# Solo_MultiCharger.net
KiCad netlist of a schematic drawn in EAGLE
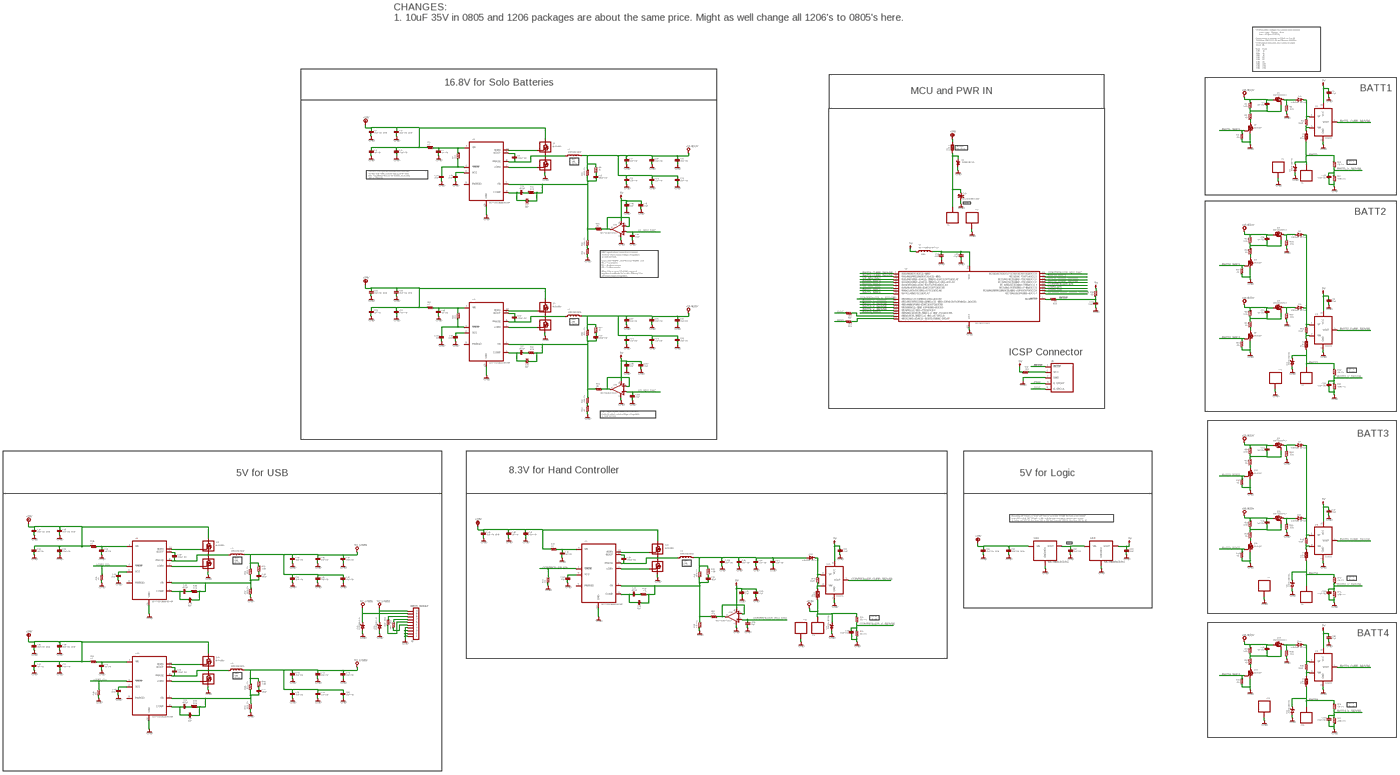
[diagram p0: schematic, sheet 1, overview]
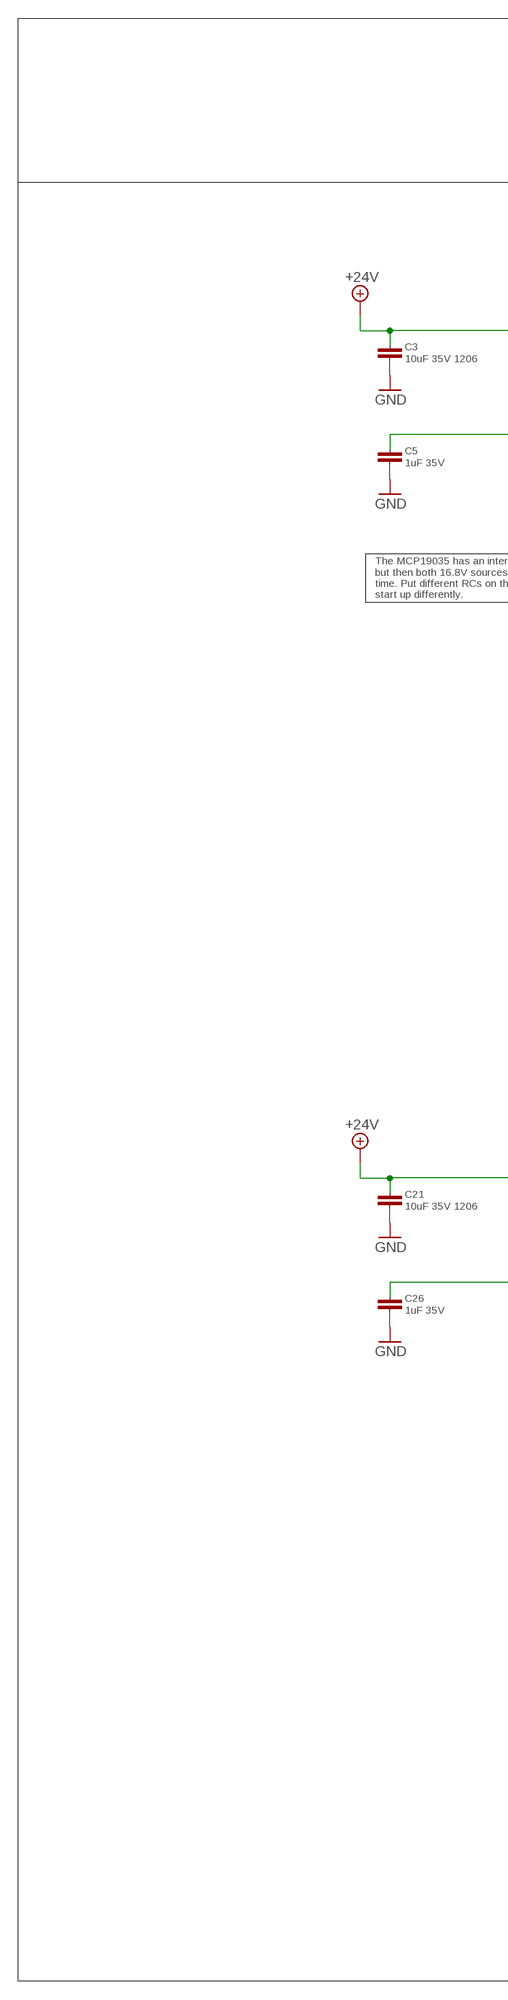
[diagram p1: schematic, sheet 1, part 1 of 8]
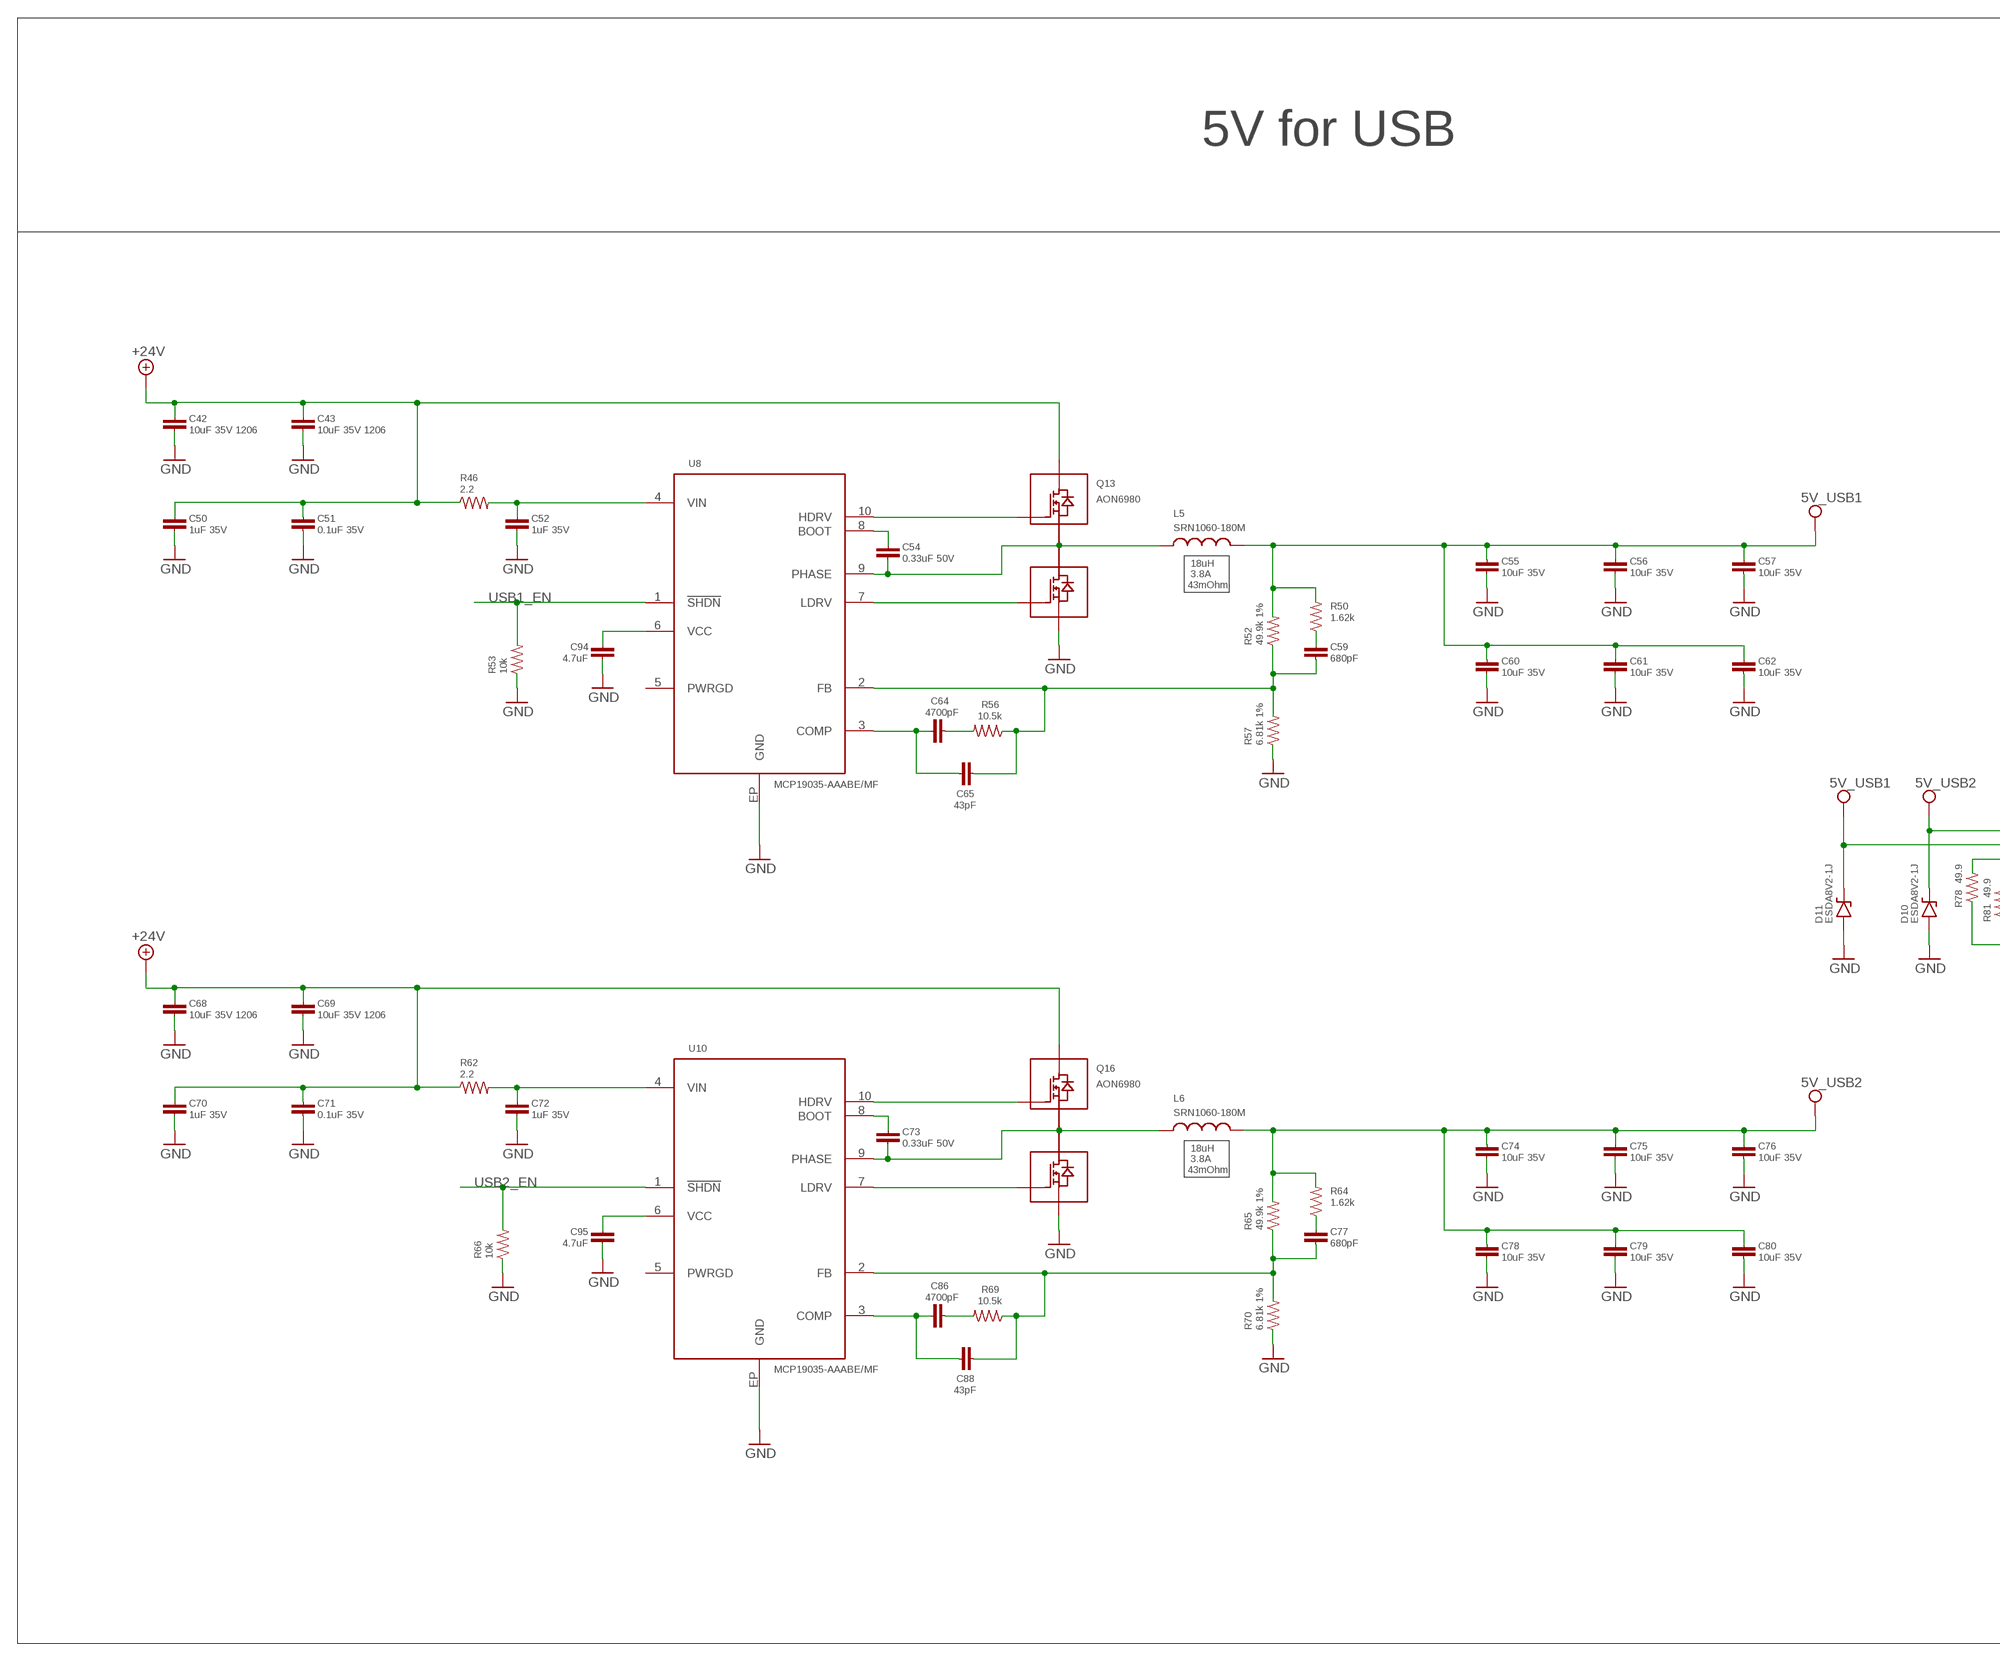
[diagram p2: schematic, sheet 1, part 2 of 8]
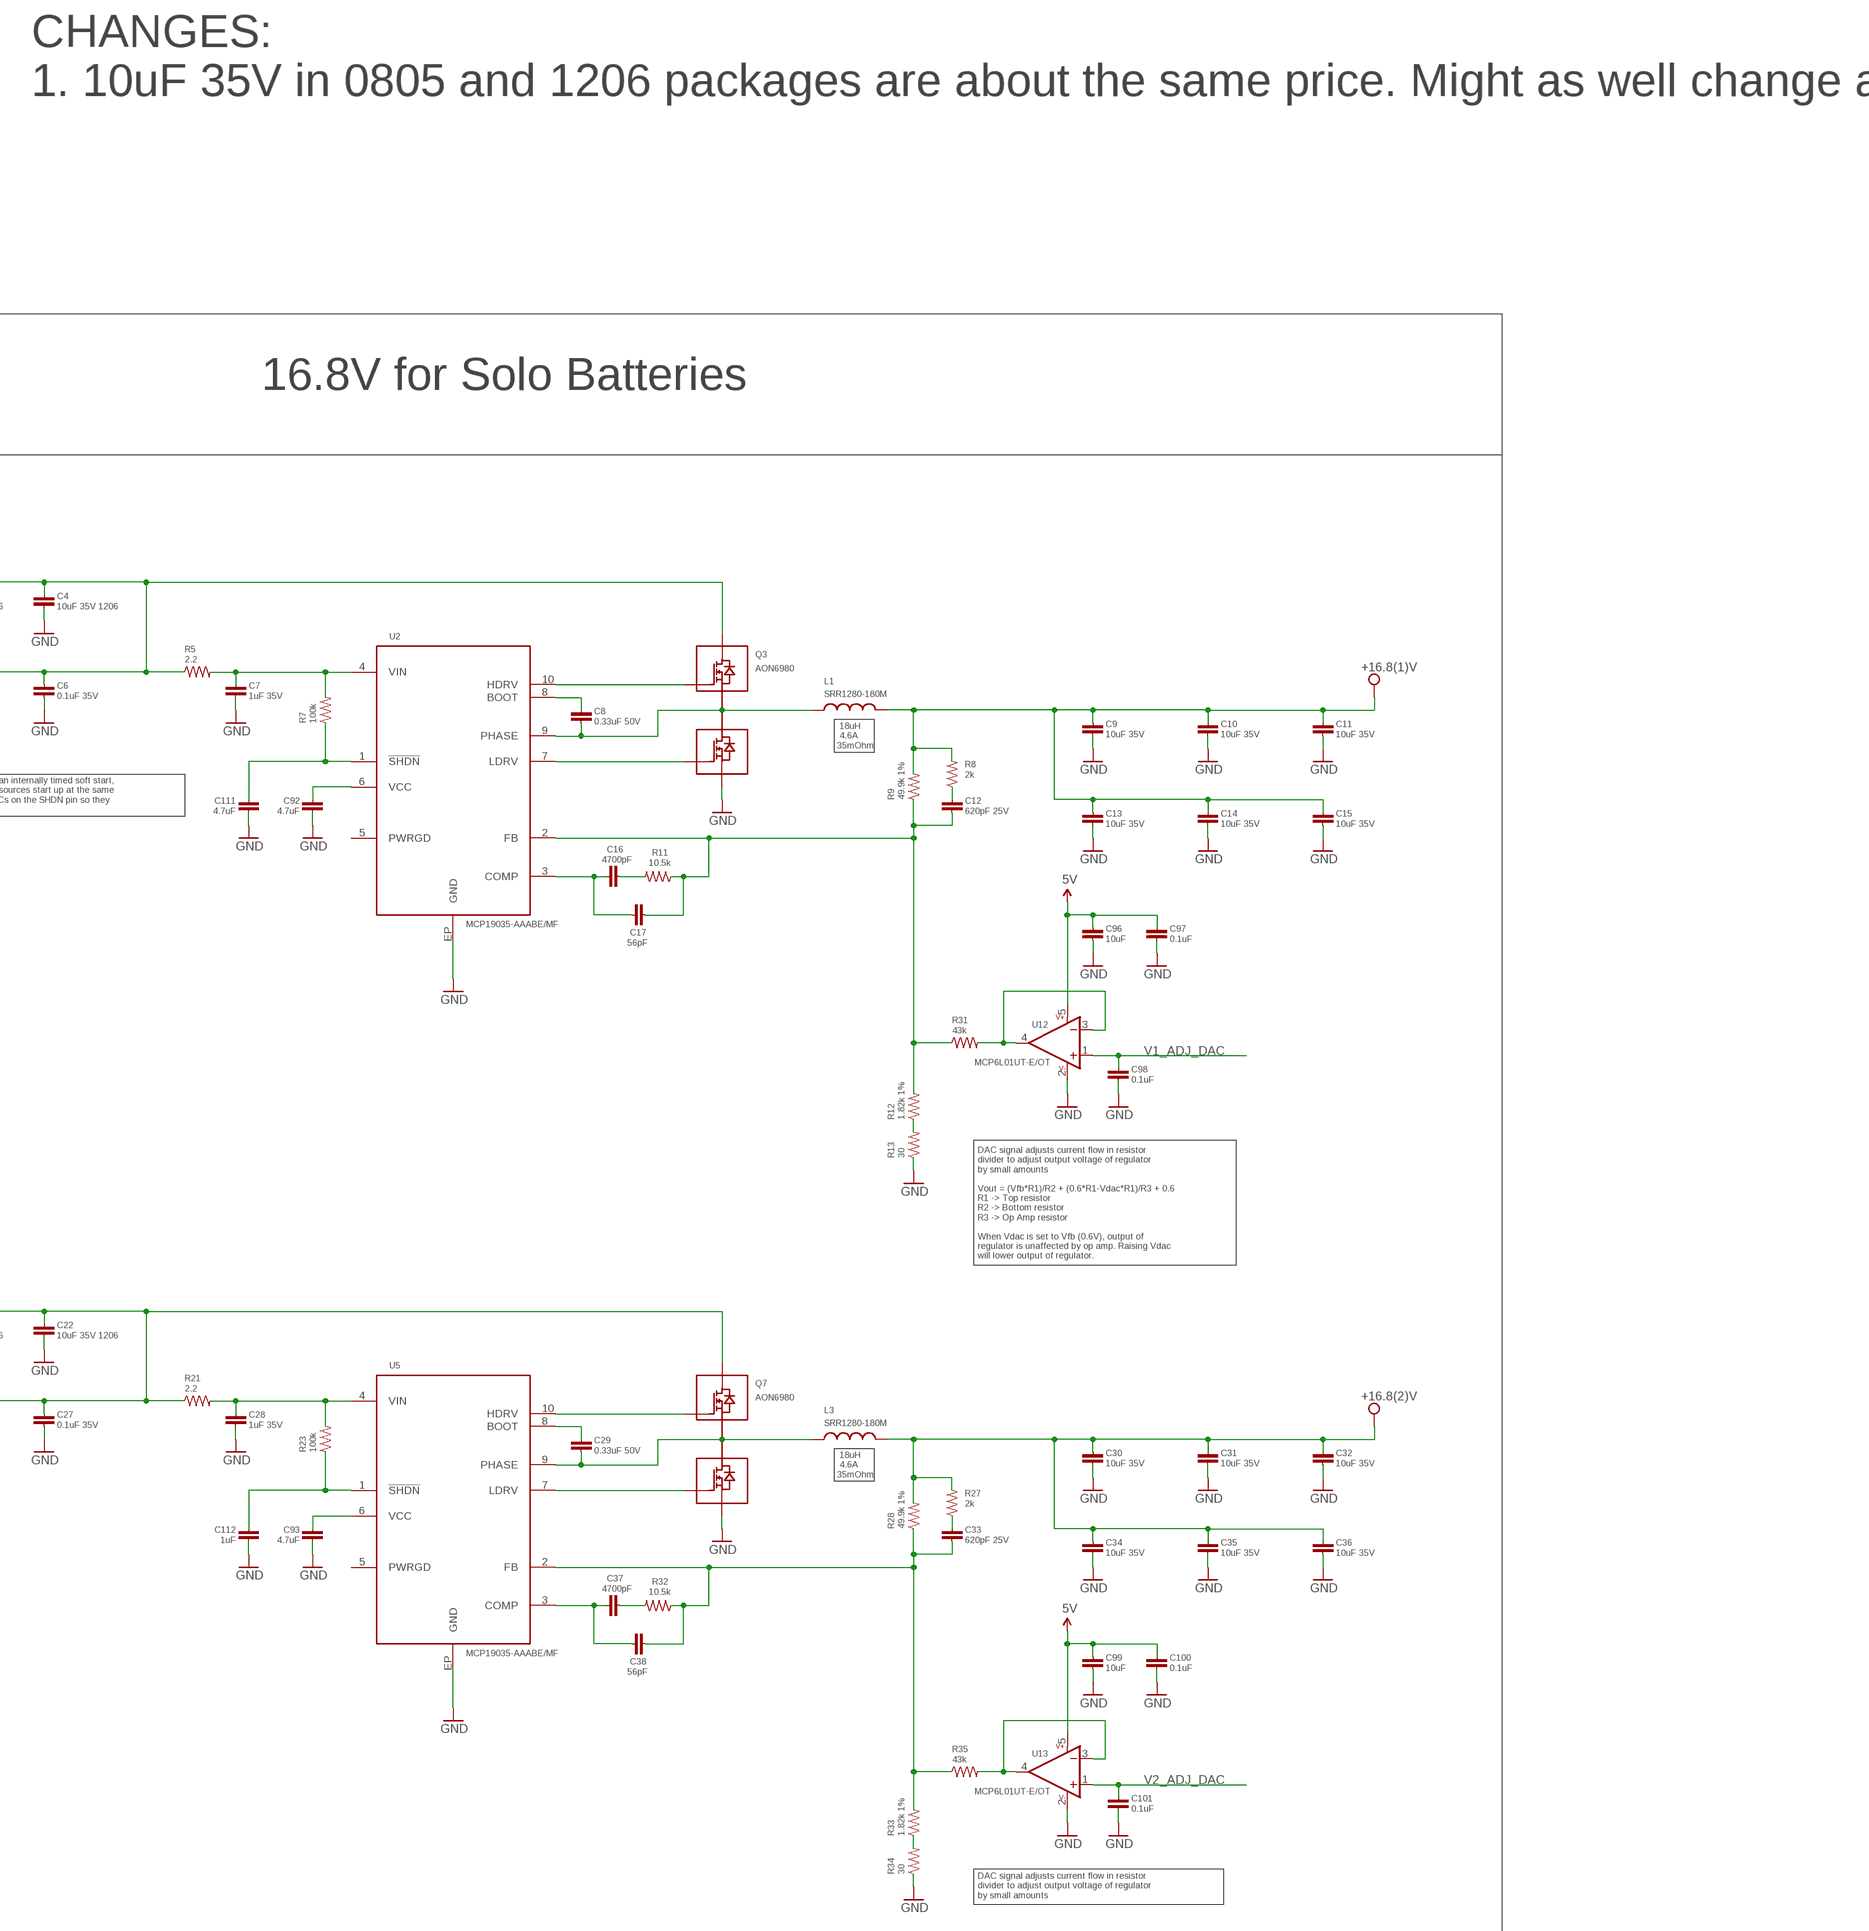
[diagram p3: schematic, sheet 1, part 3 of 8]
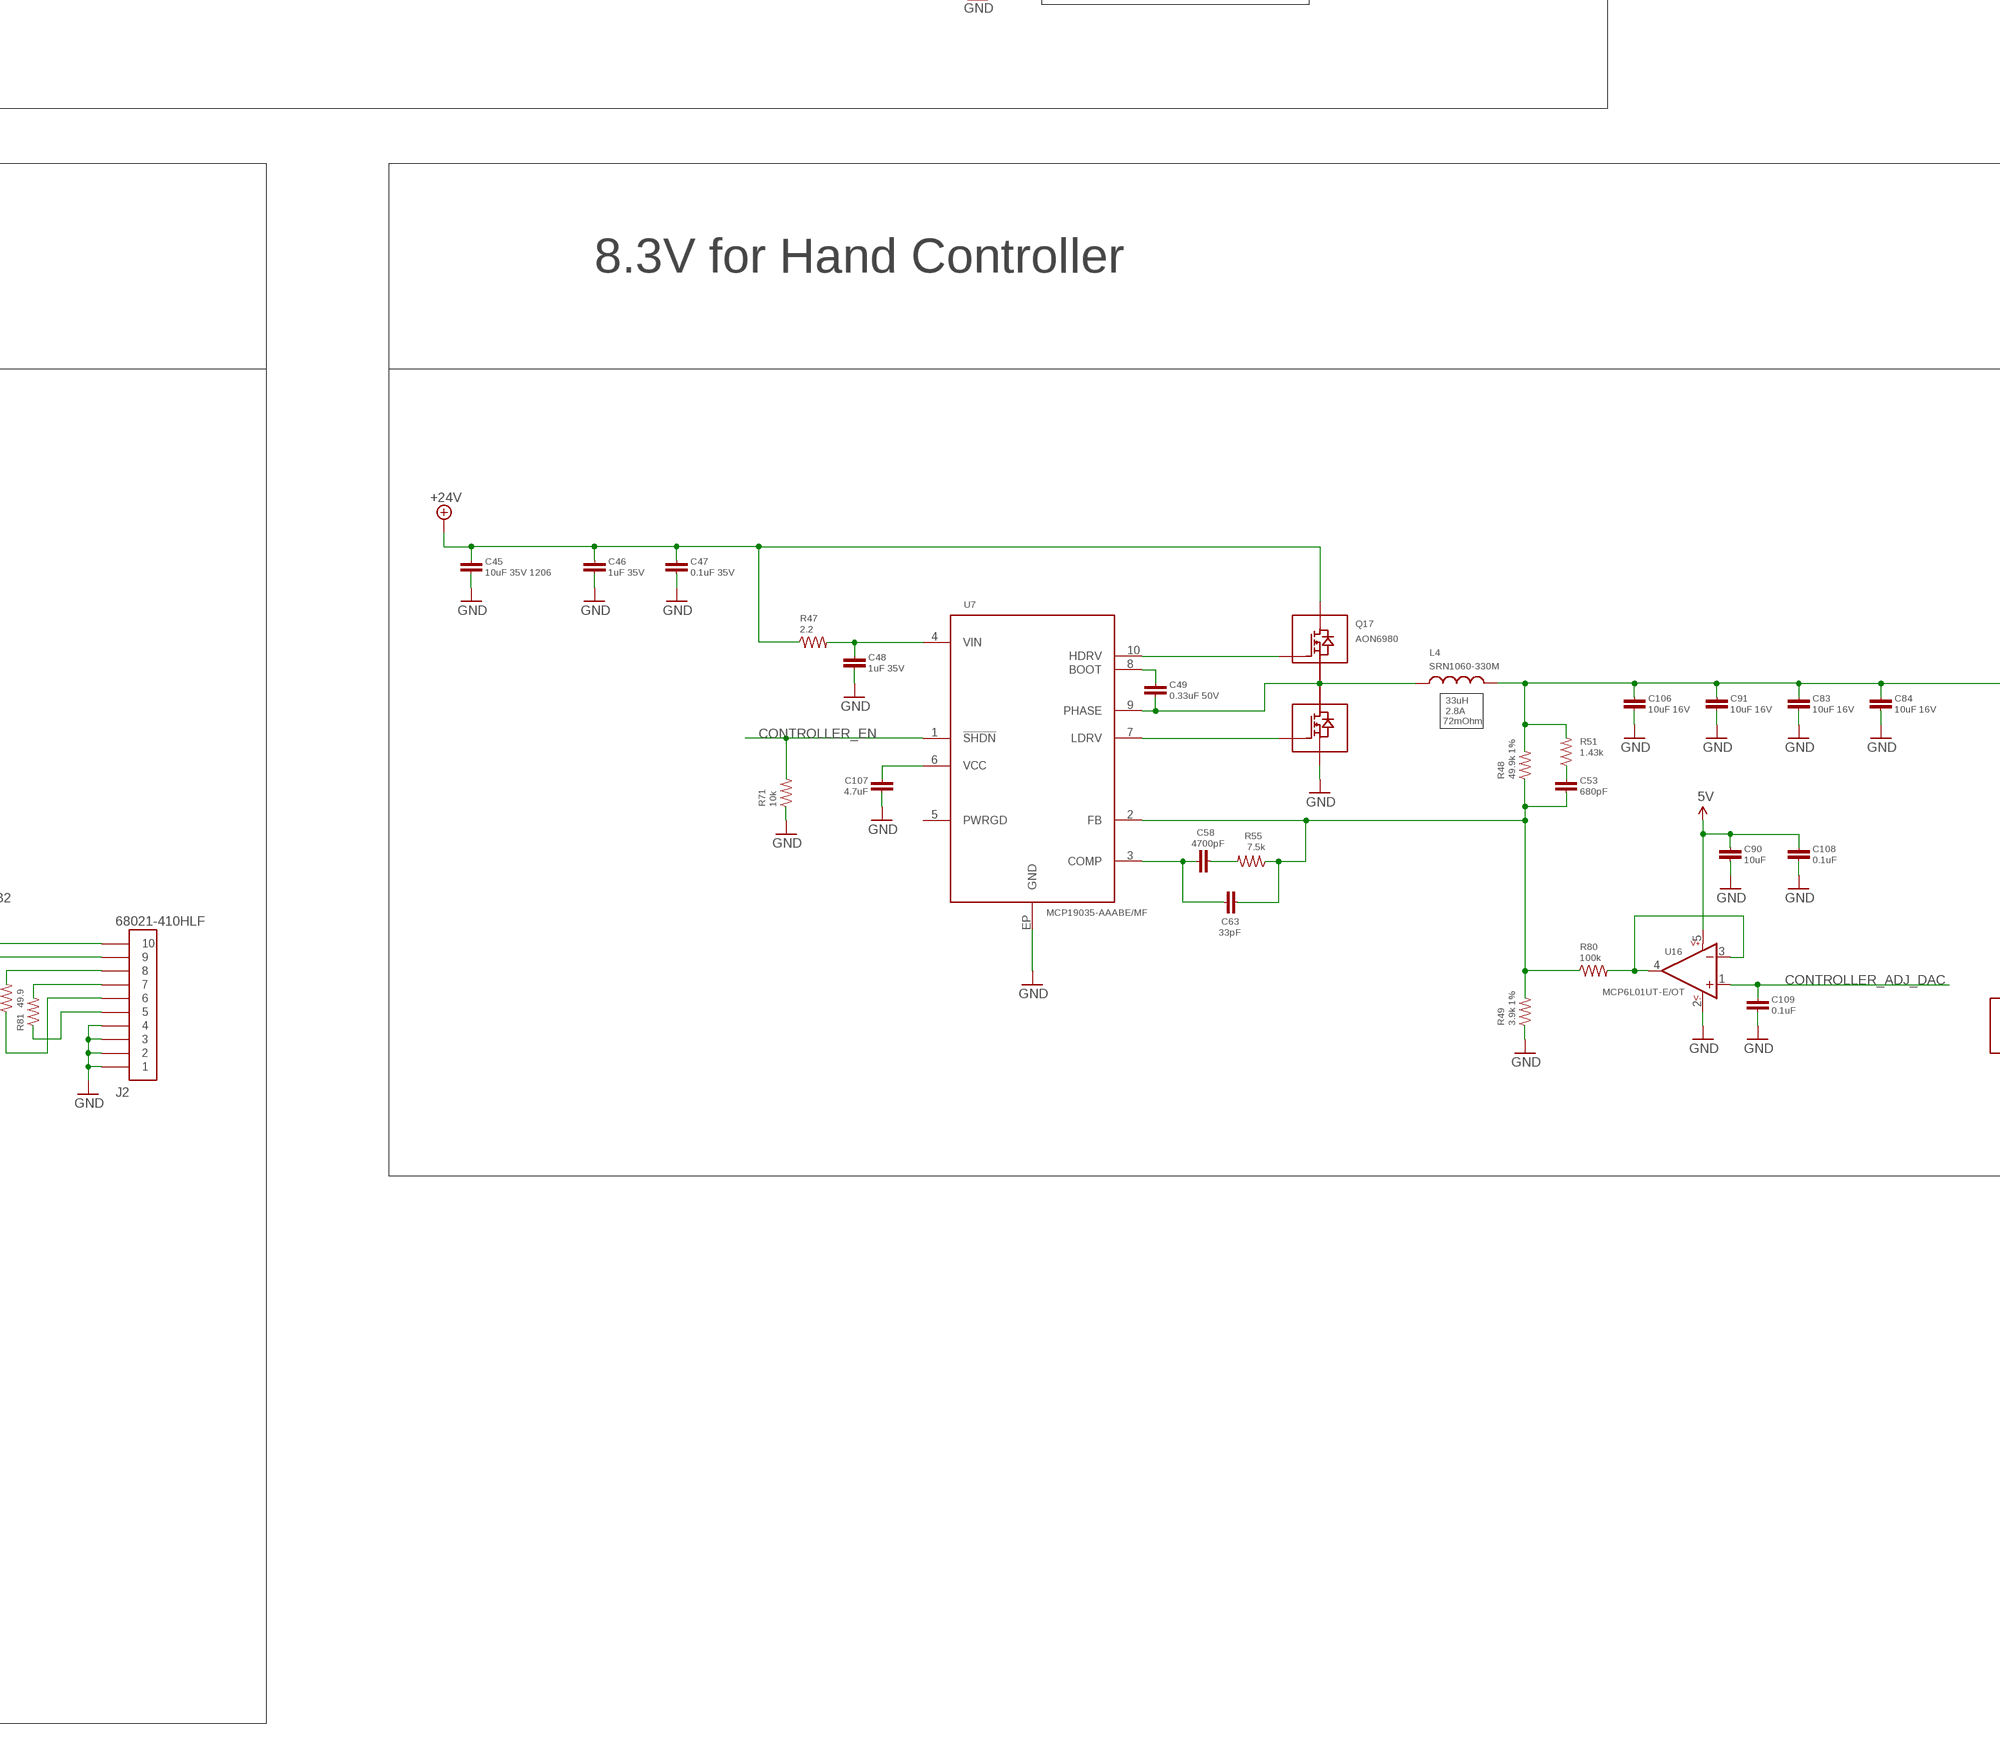
[diagram p4: schematic, sheet 1, part 4 of 8]
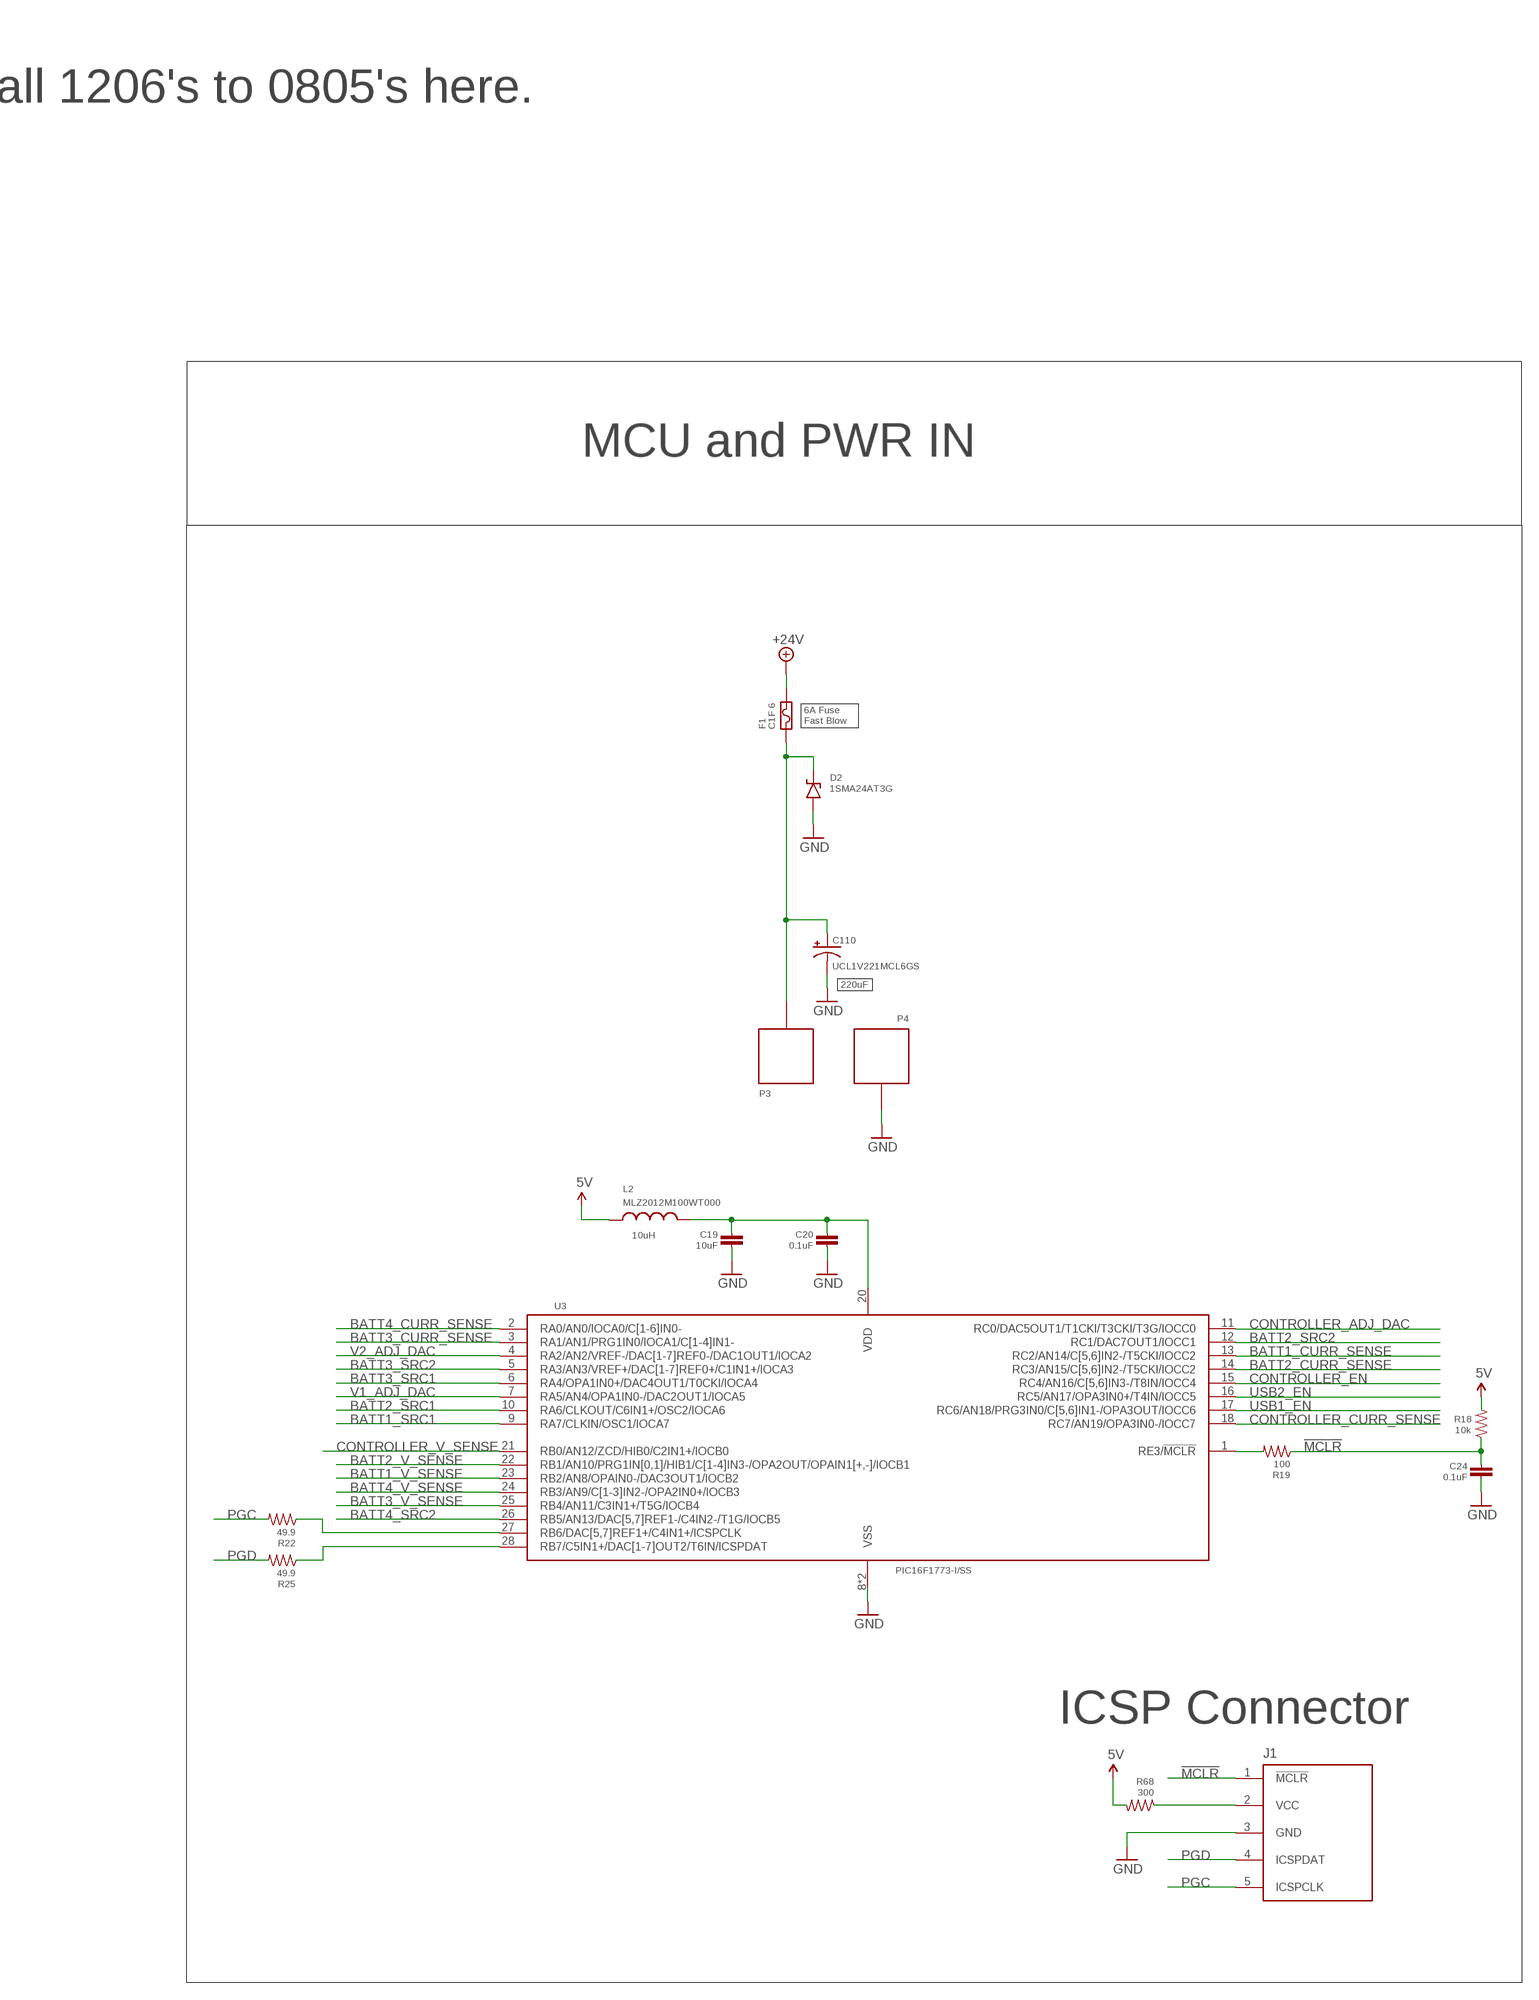
[diagram p5: schematic, sheet 1, part 5 of 8]
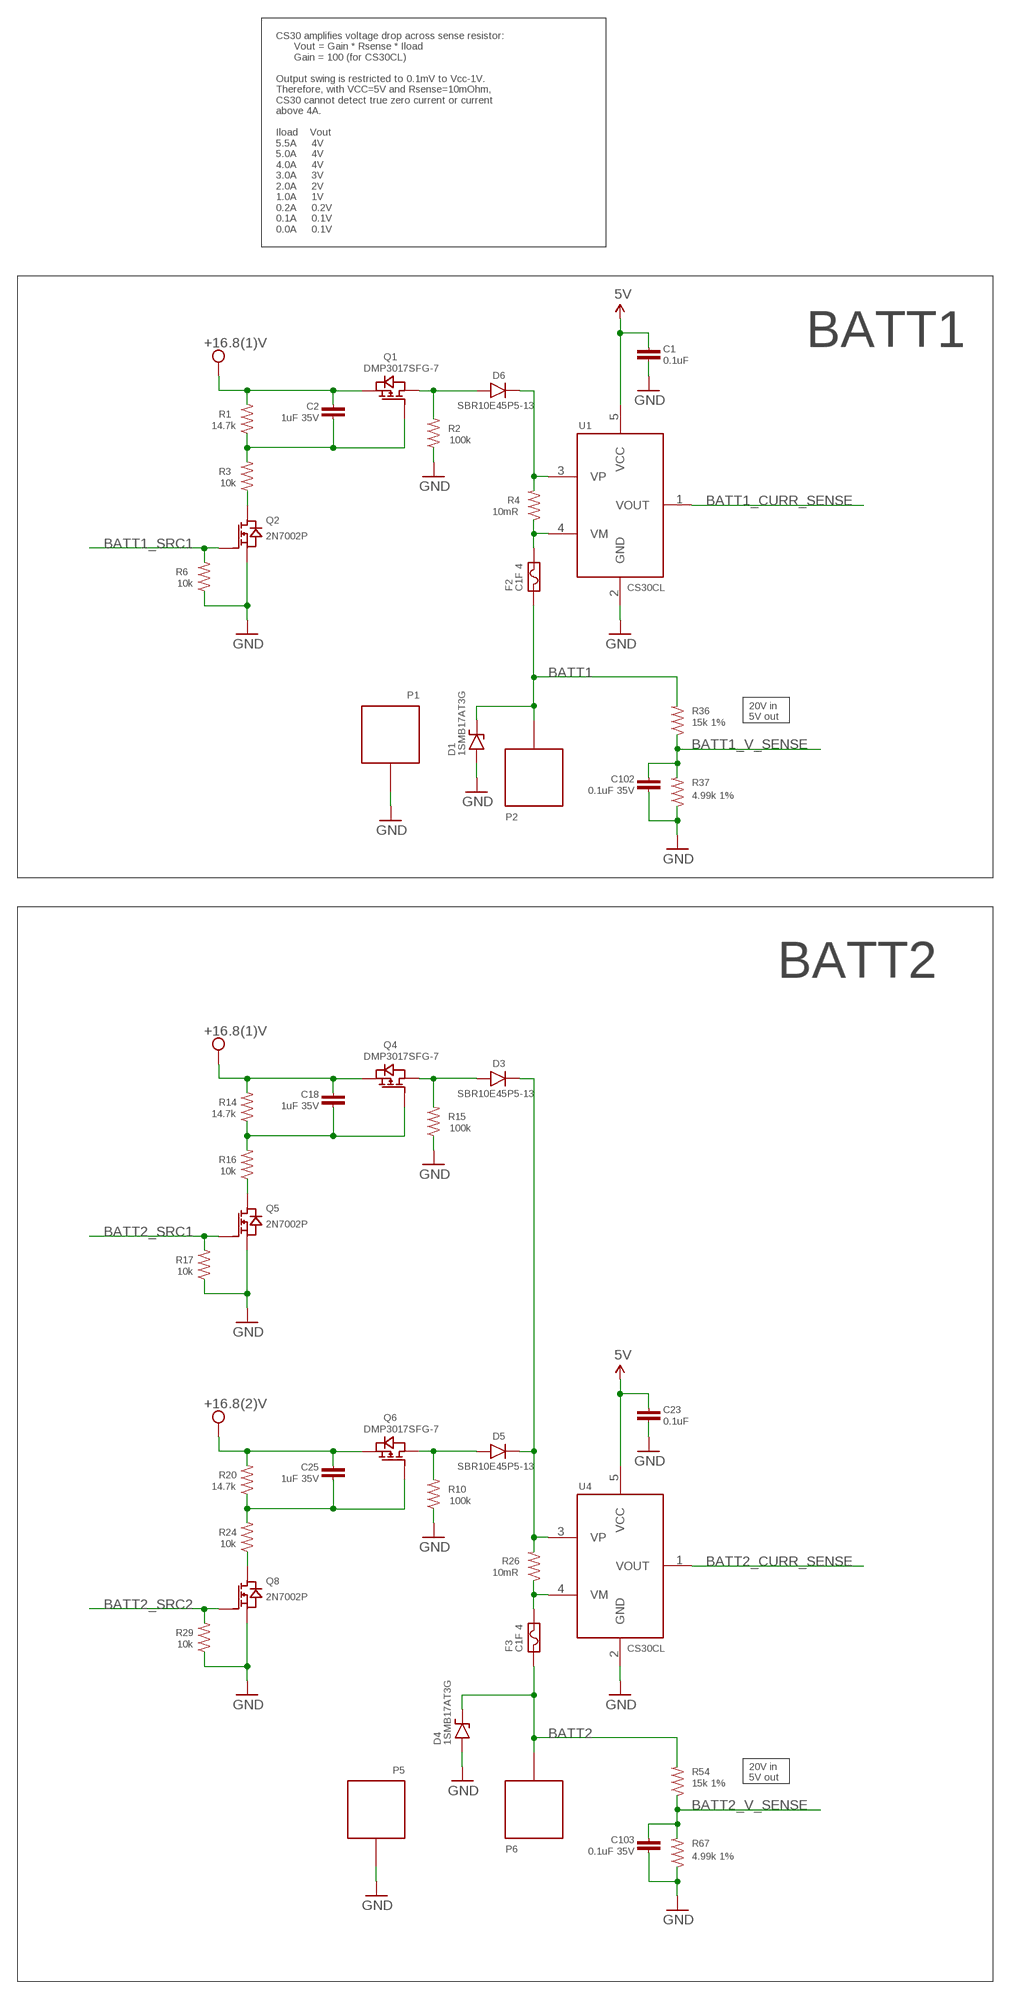
[diagram p6: schematic, sheet 1, part 6 of 8]
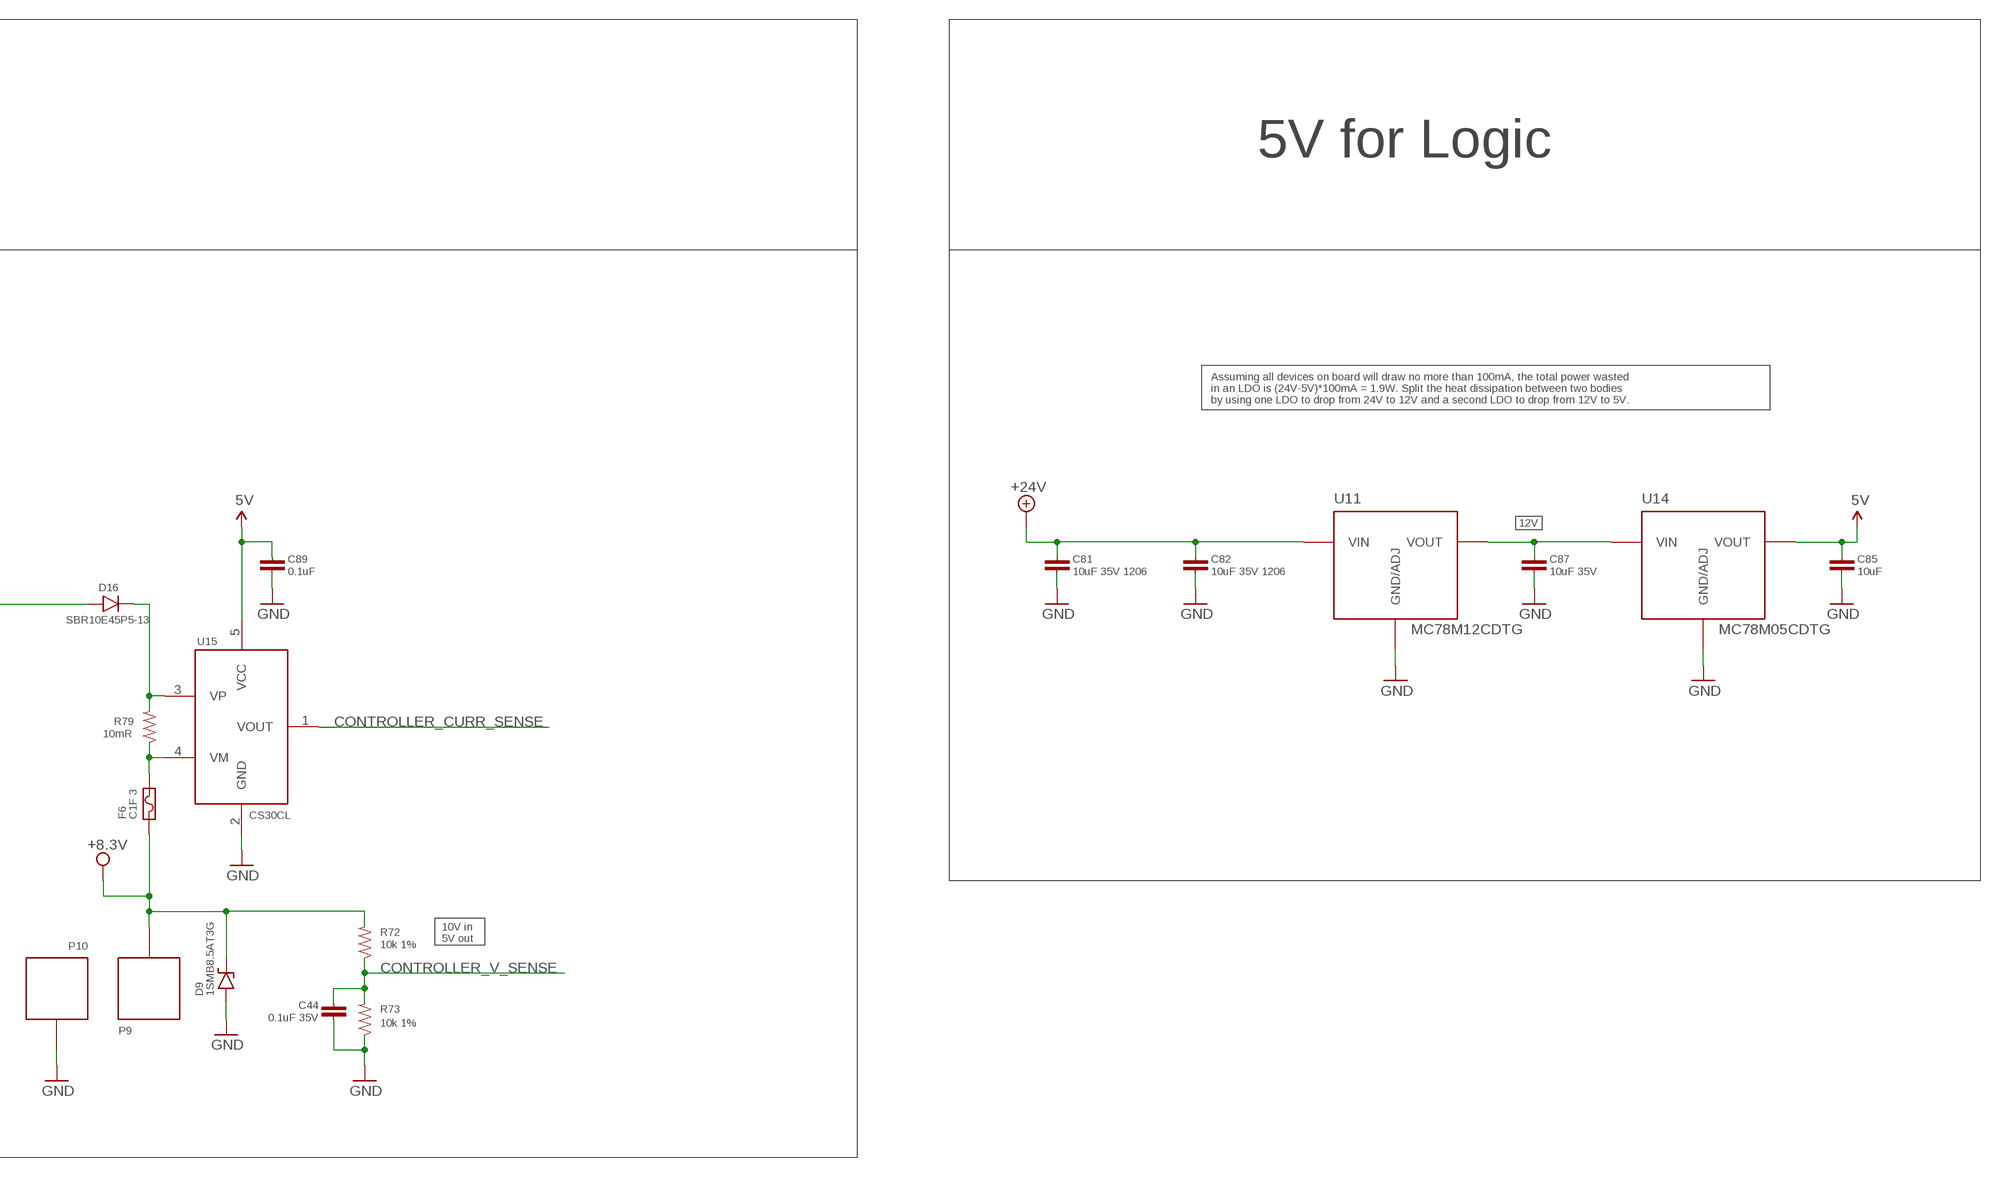
[diagram p7: schematic, sheet 1, part 7 of 8]
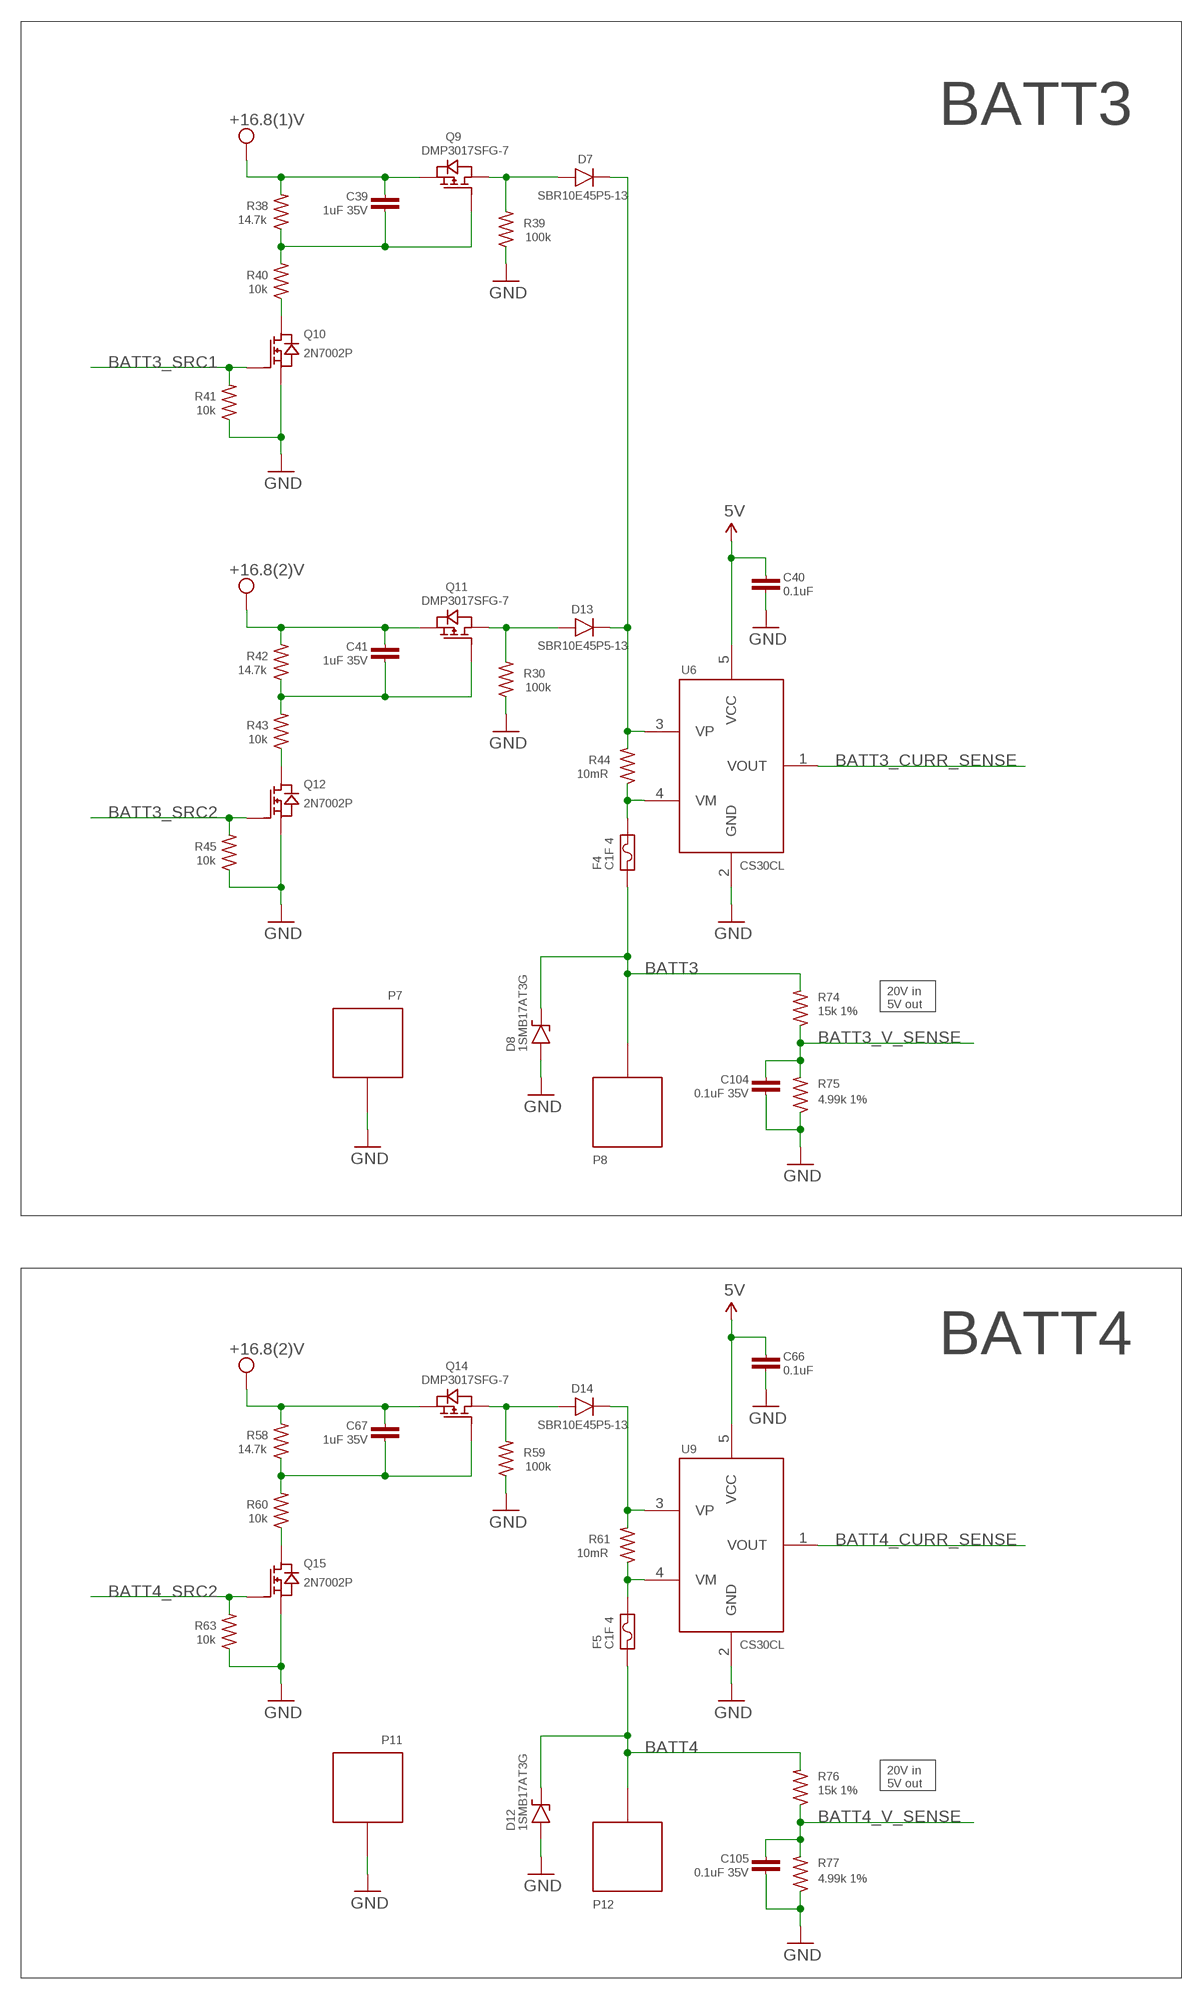
[diagram p8: schematic, sheet 1, part 8 of 8]

(export (version "E")
  (design (tool "Eeschema 10.0.6"))
  (components
    (comp (ref "C1")
      (value "0.1uF")
      (footprint "eagle-import:0805")
      (libsource (lib "eagle-import") (part "CAP_(4)"))
    )
    (comp (ref "C2")
      (value "1uF 35V")
      (footprint "eagle-import:0805")
      (libsource (lib "eagle-import") (part "CAP_(4)"))
    )
    (comp (ref "C3")
      (value "10uF 35V 1206")
      (footprint "eagle-import:1206")
      (libsource (lib "eagle-import") (part "CAP_(5)"))
    )
    (comp (ref "C4")
      (value "10uF 35V 1206")
      (footprint "eagle-import:1206")
      (libsource (lib "eagle-import") (part "CAP_(5)"))
    )
    (comp (ref "C5")
      (value "1uF 35V")
      (footprint "eagle-import:0805")
      (libsource (lib "eagle-import") (part "CAP_(4)"))
    )
    (comp (ref "C6")
      (value "0.1uF 35V")
      (footprint "eagle-import:0805")
      (libsource (lib "eagle-import") (part "CAP_(4)"))
    )
    (comp (ref "C7")
      (value "1uF 35V")
      (footprint "eagle-import:0805")
      (libsource (lib "eagle-import") (part "CAP_(4)"))
    )
    (comp (ref "C8")
      (value "0.33uF 50V")
      (footprint "eagle-import:0805")
      (libsource (lib "eagle-import") (part "CAP_(4)"))
    )
    (comp (ref "C9")
      (value "10uF 35V")
      (footprint "eagle-import:0805")
      (libsource (lib "eagle-import") (part "CAP_(4)"))
    )
    (comp (ref "C10")
      (value "10uF 35V")
      (footprint "eagle-import:0805")
      (libsource (lib "eagle-import") (part "CAP_(4)"))
    )
    (comp (ref "C11")
      (value "10uF 35V")
      (footprint "eagle-import:0805")
      (libsource (lib "eagle-import") (part "CAP_(4)"))
    )
    (comp (ref "C12")
      (value "620pF 25V")
      (footprint "eagle-import:0805")
      (libsource (lib "eagle-import") (part "CAP_(4)"))
    )
    (comp (ref "C13")
      (value "10uF 35V")
      (footprint "eagle-import:0805")
      (libsource (lib "eagle-import") (part "CAP_(4)"))
    )
    (comp (ref "C14")
      (value "10uF 35V")
      (footprint "eagle-import:0805")
      (libsource (lib "eagle-import") (part "CAP_(4)"))
    )
    (comp (ref "C15")
      (value "10uF 35V")
      (footprint "eagle-import:0805")
      (libsource (lib "eagle-import") (part "CAP_(4)"))
    )
    (comp (ref "C16")
      (value "4700pF")
      (footprint "eagle-import:0805")
      (libsource (lib "eagle-import") (part "CAP_(4)"))
    )
    (comp (ref "C17")
      (value "56pF")
      (footprint "eagle-import:0805")
      (libsource (lib "eagle-import") (part "CAP_(4)"))
    )
    (comp (ref "C18")
      (value "1uF 35V")
      (footprint "eagle-import:0805")
      (libsource (lib "eagle-import") (part "CAP_(4)"))
    )
    (comp (ref "C19")
      (value "10uF")
      (footprint "eagle-import:0805")
      (libsource (lib "eagle-import") (part "CAP_(4)"))
    )
    (comp (ref "C20")
      (value "0.1uF")
      (footprint "eagle-import:0805")
      (libsource (lib "eagle-import") (part "CAP_(4)"))
    )
    (comp (ref "C21")
      (value "10uF 35V 1206")
      (footprint "eagle-import:1206")
      (libsource (lib "eagle-import") (part "CAP_(5)"))
    )
    (comp (ref "C22")
      (value "10uF 35V 1206")
      (footprint "eagle-import:1206")
      (libsource (lib "eagle-import") (part "CAP_(5)"))
    )
    (comp (ref "C23")
      (value "0.1uF")
      (footprint "eagle-import:0805")
      (libsource (lib "eagle-import") (part "CAP_(4)"))
    )
    (comp (ref "C24")
      (value "0.1uF")
      (footprint "eagle-import:0805")
      (libsource (lib "eagle-import") (part "CAP_(4)"))
    )
    (comp (ref "C25")
      (value "1uF 35V")
      (footprint "eagle-import:0805")
      (libsource (lib "eagle-import") (part "CAP_(4)"))
    )
    (comp (ref "C26")
      (value "1uF 35V")
      (footprint "eagle-import:0805")
      (libsource (lib "eagle-import") (part "CAP_(4)"))
    )
    (comp (ref "C27")
      (value "0.1uF 35V")
      (footprint "eagle-import:0805")
      (libsource (lib "eagle-import") (part "CAP_(4)"))
    )
    (comp (ref "C28")
      (value "1uF 35V")
      (footprint "eagle-import:0805")
      (libsource (lib "eagle-import") (part "CAP_(4)"))
    )
    (comp (ref "C29")
      (value "0.33uF 50V")
      (footprint "eagle-import:0805")
      (libsource (lib "eagle-import") (part "CAP_(4)"))
    )
    (comp (ref "C30")
      (value "10uF 35V")
      (footprint "eagle-import:0805")
      (libsource (lib "eagle-import") (part "CAP_(4)"))
    )
    (comp (ref "C31")
      (value "10uF 35V")
      (footprint "eagle-import:0805")
      (libsource (lib "eagle-import") (part "CAP_(4)"))
    )
    (comp (ref "C32")
      (value "10uF 35V")
      (footprint "eagle-import:0805")
      (libsource (lib "eagle-import") (part "CAP_(4)"))
    )
    (comp (ref "C33")
      (value "620pF 25V")
      (footprint "eagle-import:0805")
      (libsource (lib "eagle-import") (part "CAP_(4)"))
    )
    (comp (ref "C34")
      (value "10uF 35V")
      (footprint "eagle-import:0805")
      (libsource (lib "eagle-import") (part "CAP_(4)"))
    )
    (comp (ref "C35")
      (value "10uF 35V")
      (footprint "eagle-import:0805")
      (libsource (lib "eagle-import") (part "CAP_(4)"))
    )
    (comp (ref "C36")
      (value "10uF 35V")
      (footprint "eagle-import:0805")
      (libsource (lib "eagle-import") (part "CAP_(4)"))
    )
    (comp (ref "C37")
      (value "4700pF")
      (footprint "eagle-import:0805")
      (libsource (lib "eagle-import") (part "CAP_(4)"))
    )
    (comp (ref "C38")
      (value "56pF")
      (footprint "eagle-import:0805")
      (libsource (lib "eagle-import") (part "CAP_(4)"))
    )
    (comp (ref "C39")
      (value "1uF 35V")
      (footprint "eagle-import:0805")
      (libsource (lib "eagle-import") (part "CAP_(4)"))
    )
    (comp (ref "C40")
      (value "0.1uF")
      (footprint "eagle-import:0805")
      (libsource (lib "eagle-import") (part "CAP_(4)"))
    )
    (comp (ref "C41")
      (value "1uF 35V")
      (footprint "eagle-import:0805")
      (libsource (lib "eagle-import") (part "CAP_(4)"))
    )
    (comp (ref "C42")
      (value "10uF 35V 1206")
      (footprint "eagle-import:1206")
      (libsource (lib "eagle-import") (part "CAP_(5)"))
    )
    (comp (ref "C43")
      (value "10uF 35V 1206")
      (footprint "eagle-import:1206")
      (libsource (lib "eagle-import") (part "CAP_(5)"))
    )
    (comp (ref "C44")
      (value "0.1uF 35V")
      (footprint "eagle-import:0805")
      (libsource (lib "eagle-import") (part "CAP_(4)"))
    )
    (comp (ref "C45")
      (value "10uF 35V 1206")
      (footprint "eagle-import:1206")
      (libsource (lib "eagle-import") (part "CAP_(5)"))
    )
    (comp (ref "C46")
      (value "1uF 35V")
      (footprint "eagle-import:0805")
      (libsource (lib "eagle-import") (part "CAP_(4)"))
    )
    (comp (ref "C47")
      (value "0.1uF 35V")
      (footprint "eagle-import:0805")
      (libsource (lib "eagle-import") (part "CAP_(4)"))
    )
    (comp (ref "C48")
      (value "1uF 35V")
      (footprint "eagle-import:0805")
      (libsource (lib "eagle-import") (part "CAP_(4)"))
    )
    (comp (ref "C49")
      (value "0.33uF 50V")
      (footprint "eagle-import:0805")
      (libsource (lib "eagle-import") (part "CAP_(4)"))
    )
    (comp (ref "C50")
      (value "1uF 35V")
      (footprint "eagle-import:0805")
      (libsource (lib "eagle-import") (part "CAP_(4)"))
    )
    (comp (ref "C51")
      (value "0.1uF 35V")
      (footprint "eagle-import:0805")
      (libsource (lib "eagle-import") (part "CAP_(4)"))
    )
    (comp (ref "C52")
      (value "1uF 35V")
      (footprint "eagle-import:0805")
      (libsource (lib "eagle-import") (part "CAP_(4)"))
    )
    (comp (ref "C53")
      (value "680pF")
      (footprint "eagle-import:0805")
      (libsource (lib "eagle-import") (part "CAP_(4)"))
    )
    (comp (ref "C54")
      (value "0.33uF 50V")
      (footprint "eagle-import:0805")
      (libsource (lib "eagle-import") (part "CAP_(4)"))
    )
    (comp (ref "C55")
      (value "10uF 35V")
      (footprint "eagle-import:0805")
      (libsource (lib "eagle-import") (part "CAP_(4)"))
    )
    (comp (ref "C56")
      (value "10uF 35V")
      (footprint "eagle-import:0805")
      (libsource (lib "eagle-import") (part "CAP_(4)"))
    )
    (comp (ref "C57")
      (value "10uF 35V")
      (footprint "eagle-import:0805")
      (libsource (lib "eagle-import") (part "CAP_(4)"))
    )
    (comp (ref "C58")
      (value "4700pF")
      (footprint "eagle-import:0805")
      (libsource (lib "eagle-import") (part "CAP_(4)"))
    )
    (comp (ref "C59")
      (value "680pF")
      (footprint "eagle-import:0805")
      (libsource (lib "eagle-import") (part "CAP_(4)"))
    )
    (comp (ref "C60")
      (value "10uF 35V")
      (footprint "eagle-import:0805")
      (libsource (lib "eagle-import") (part "CAP_(4)"))
    )
    (comp (ref "C61")
      (value "10uF 35V")
      (footprint "eagle-import:0805")
      (libsource (lib "eagle-import") (part "CAP_(4)"))
    )
    (comp (ref "C62")
      (value "10uF 35V")
      (footprint "eagle-import:0805")
      (libsource (lib "eagle-import") (part "CAP_(4)"))
    )
    (comp (ref "C63")
      (value "33pF")
      (footprint "eagle-import:0805")
      (libsource (lib "eagle-import") (part "CAP_(4)"))
    )
    (comp (ref "C64")
      (value "4700pF")
      (footprint "eagle-import:0805")
      (libsource (lib "eagle-import") (part "CAP_(4)"))
    )
    (comp (ref "C65")
      (value "43pF")
      (footprint "eagle-import:0805")
      (libsource (lib "eagle-import") (part "CAP_(4)"))
    )
    (comp (ref "C66")
      (value "0.1uF")
      (footprint "eagle-import:0805")
      (libsource (lib "eagle-import") (part "CAP_(4)"))
    )
    (comp (ref "C67")
      (value "1uF 35V")
      (footprint "eagle-import:0805")
      (libsource (lib "eagle-import") (part "CAP_(4)"))
    )
    (comp (ref "C68")
      (value "10uF 35V 1206")
      (footprint "eagle-import:1206")
      (libsource (lib "eagle-import") (part "CAP_(5)"))
    )
    (comp (ref "C69")
      (value "10uF 35V 1206")
      (footprint "eagle-import:1206")
      (libsource (lib "eagle-import") (part "CAP_(5)"))
    )
    (comp (ref "C70")
      (value "1uF 35V")
      (footprint "eagle-import:0805")
      (libsource (lib "eagle-import") (part "CAP_(4)"))
    )
    (comp (ref "C71")
      (value "0.1uF 35V")
      (footprint "eagle-import:0805")
      (libsource (lib "eagle-import") (part "CAP_(4)"))
    )
    (comp (ref "C72")
      (value "1uF 35V")
      (footprint "eagle-import:0805")
      (libsource (lib "eagle-import") (part "CAP_(4)"))
    )
    (comp (ref "C73")
      (value "0.33uF 50V")
      (footprint "eagle-import:0805")
      (libsource (lib "eagle-import") (part "CAP_(4)"))
    )
    (comp (ref "C74")
      (value "10uF 35V")
      (footprint "eagle-import:0805")
      (libsource (lib "eagle-import") (part "CAP_(4)"))
    )
    (comp (ref "C75")
      (value "10uF 35V")
      (footprint "eagle-import:0805")
      (libsource (lib "eagle-import") (part "CAP_(4)"))
    )
    (comp (ref "C76")
      (value "10uF 35V")
      (footprint "eagle-import:0805")
      (libsource (lib "eagle-import") (part "CAP_(4)"))
    )
    (comp (ref "C77")
      (value "680pF")
      (footprint "eagle-import:0805")
      (libsource (lib "eagle-import") (part "CAP_(4)"))
    )
    (comp (ref "C78")
      (value "10uF 35V")
      (footprint "eagle-import:0805")
      (libsource (lib "eagle-import") (part "CAP_(4)"))
    )
    (comp (ref "C79")
      (value "10uF 35V")
      (footprint "eagle-import:0805")
      (libsource (lib "eagle-import") (part "CAP_(4)"))
    )
    (comp (ref "C80")
      (value "10uF 35V")
      (footprint "eagle-import:0805")
      (libsource (lib "eagle-import") (part "CAP_(4)"))
    )
    (comp (ref "C81")
      (value "10uF 35V 1206")
      (footprint "eagle-import:1206")
      (libsource (lib "eagle-import") (part "CAP_(5)"))
    )
    (comp (ref "C82")
      (value "10uF 35V 1206")
      (footprint "eagle-import:1206")
      (libsource (lib "eagle-import") (part "CAP_(5)"))
    )
    (comp (ref "C83")
      (value "10uF 16V")
      (footprint "eagle-import:0805")
      (libsource (lib "eagle-import") (part "CAP_(4)"))
    )
    (comp (ref "C84")
      (value "10uF 16V")
      (footprint "eagle-import:0805")
      (libsource (lib "eagle-import") (part "CAP_(4)"))
    )
    (comp (ref "C85")
      (value "10uF")
      (footprint "eagle-import:0805")
      (libsource (lib "eagle-import") (part "CAP_(4)"))
    )
    (comp (ref "C86")
      (value "4700pF")
      (footprint "eagle-import:0805")
      (libsource (lib "eagle-import") (part "CAP_(4)"))
    )
    (comp (ref "C87")
      (value "10uF 35V")
      (footprint "eagle-import:0805")
      (libsource (lib "eagle-import") (part "CAP_(4)"))
    )
    (comp (ref "C88")
      (value "43pF")
      (footprint "eagle-import:0805")
      (libsource (lib "eagle-import") (part "CAP_(4)"))
    )
    (comp (ref "C89")
      (value "0.1uF")
      (footprint "eagle-import:0805")
      (libsource (lib "eagle-import") (part "CAP_(4)"))
    )
    (comp (ref "C90")
      (value "10uF")
      (footprint "eagle-import:0805")
      (libsource (lib "eagle-import") (part "CAP_(4)"))
    )
    (comp (ref "C91")
      (value "10uF 16V")
      (footprint "eagle-import:0805")
      (libsource (lib "eagle-import") (part "CAP_(4)"))
    )
    (comp (ref "C92")
      (value "4.7uF")
      (footprint "eagle-import:0805")
      (libsource (lib "eagle-import") (part "CAP_(4)"))
    )
    (comp (ref "C93")
      (value "4.7uF")
      (footprint "eagle-import:0805")
      (libsource (lib "eagle-import") (part "CAP_(4)"))
    )
    (comp (ref "C94")
      (value "4.7uF")
      (footprint "eagle-import:0805")
      (libsource (lib "eagle-import") (part "CAP_(4)"))
    )
    (comp (ref "C95")
      (value "4.7uF")
      (footprint "eagle-import:0805")
      (libsource (lib "eagle-import") (part "CAP_(4)"))
    )
    (comp (ref "C96")
      (value "10uF")
      (footprint "eagle-import:0805")
      (libsource (lib "eagle-import") (part "CAP_(4)"))
    )
    (comp (ref "C97")
      (value "0.1uF")
      (footprint "eagle-import:0805")
      (libsource (lib "eagle-import") (part "CAP_(4)"))
    )
    (comp (ref "C98")
      (value "0.1uF")
      (footprint "eagle-import:0805")
      (libsource (lib "eagle-import") (part "CAP_(4)"))
    )
    (comp (ref "C99")
      (value "10uF")
      (footprint "eagle-import:0805")
      (libsource (lib "eagle-import") (part "CAP_(4)"))
    )
    (comp (ref "C100")
      (value "0.1uF")
      (footprint "eagle-import:0805")
      (libsource (lib "eagle-import") (part "CAP_(4)"))
    )
    (comp (ref "C101")
      (value "0.1uF")
      (footprint "eagle-import:0805")
      (libsource (lib "eagle-import") (part "CAP_(4)"))
    )
    (comp (ref "C102")
      (value "0.1uF 35V")
      (footprint "eagle-import:0805")
      (libsource (lib "eagle-import") (part "CAP_(4)"))
    )
    (comp (ref "C103")
      (value "0.1uF 35V")
      (footprint "eagle-import:0805")
      (libsource (lib "eagle-import") (part "CAP_(4)"))
    )
    (comp (ref "C104")
      (value "0.1uF 35V")
      (footprint "eagle-import:0805")
      (libsource (lib "eagle-import") (part "CAP_(4)"))
    )
    (comp (ref "C105")
      (value "0.1uF 35V")
      (footprint "eagle-import:0805")
      (libsource (lib "eagle-import") (part "CAP_(4)"))
    )
    (comp (ref "C106")
      (value "10uF 16V")
      (footprint "eagle-import:0805")
      (libsource (lib "eagle-import") (part "CAP_(4)"))
    )
    (comp (ref "C107")
      (value "4.7uF")
      (footprint "eagle-import:0805")
      (libsource (lib "eagle-import") (part "CAP_(4)"))
    )
    (comp (ref "C108")
      (value "0.1uF")
      (footprint "eagle-import:0805")
      (libsource (lib "eagle-import") (part "CAP_(4)"))
    )
    (comp (ref "C109")
      (value "0.1uF")
      (footprint "eagle-import:0805")
      (libsource (lib "eagle-import") (part "CAP_(4)"))
    )
    (comp (ref "C110")
      (value "UCL1V221MCL6GS")
      (footprint "eagle-import:NICHICON_10MM")
      (libsource (lib "eagle-import") (part "CAP_POL_(12)"))
    )
    (comp (ref "C111")
      (value "4.7uF")
      (footprint "eagle-import:0805")
      (libsource (lib "eagle-import") (part "CAP_(4)"))
    )
    (comp (ref "C112")
      (value "1uF")
      (footprint "eagle-import:0805")
      (libsource (lib "eagle-import") (part "CAP_(4)"))
    )
    (comp (ref "D1")
      (value "1SMB17AT3G")
      (footprint "eagle-import:DO-214AA")
      (libsource (lib "eagle-import") (part "ZENER_(2)"))
    )
    (comp (ref "D2")
      (value "1SMA24AT3G")
      (footprint "eagle-import:DO-214AC")
      (libsource (lib "eagle-import") (part "ZENER_(4)"))
    )
    (comp (ref "D3")
      (value "SBR10E45P5-13")
      (footprint "eagle-import:POWERDI-5")
      (libsource (lib "eagle-import") (part "DIODE_(4)"))
    )
    (comp (ref "D4")
      (value "1SMB17AT3G")
      (footprint "eagle-import:DO-214AA")
      (libsource (lib "eagle-import") (part "ZENER_(2)"))
    )
    (comp (ref "D5")
      (value "SBR10E45P5-13")
      (footprint "eagle-import:POWERDI-5")
      (libsource (lib "eagle-import") (part "DIODE_(4)"))
    )
    (comp (ref "D6")
      (value "SBR10E45P5-13")
      (footprint "eagle-import:POWERDI-5")
      (libsource (lib "eagle-import") (part "DIODE_(4)"))
    )
    (comp (ref "D7")
      (value "SBR10E45P5-13")
      (footprint "eagle-import:POWERDI-5")
      (libsource (lib "eagle-import") (part "DIODE_(4)"))
    )
    (comp (ref "D8")
      (value "1SMB17AT3G")
      (footprint "eagle-import:DO-214AA")
      (libsource (lib "eagle-import") (part "ZENER_(2)"))
    )
    (comp (ref "D9")
      (value "1SMB8.5AT3G")
      (footprint "eagle-import:DO-214AA")
      (libsource (lib "eagle-import") (part "ZENER_(2)"))
    )
    (comp (ref "D10")
      (value "ESDA8V2-1J")
      (footprint "eagle-import:SOD-323")
      (libsource (lib "eagle-import") (part "ZENER_(5)"))
    )
    (comp (ref "D11")
      (value "ESDA8V2-1J")
      (footprint "eagle-import:SOD-323")
      (libsource (lib "eagle-import") (part "ZENER_(5)"))
    )
    (comp (ref "D12")
      (value "1SMB17AT3G")
      (footprint "eagle-import:DO-214AA")
      (libsource (lib "eagle-import") (part "ZENER_(2)"))
    )
    (comp (ref "D13")
      (value "SBR10E45P5-13")
      (footprint "eagle-import:POWERDI-5")
      (libsource (lib "eagle-import") (part "DIODE_(4)"))
    )
    (comp (ref "D14")
      (value "SBR10E45P5-13")
      (footprint "eagle-import:POWERDI-5")
      (libsource (lib "eagle-import") (part "DIODE_(4)"))
    )
    (comp (ref "D16")
      (value "SBR10E45P5-13")
      (footprint "eagle-import:POWERDI-5")
      (libsource (lib "eagle-import") (part "DIODE_(4)"))
    )
    (comp (ref "F1")
      (value "C1F 6")
      (footprint "eagle-import:1206")
      (libsource (lib "eagle-import") (part "FUSE_(2)"))
    )
    (comp (ref "F2")
      (value "C1F 4")
      (footprint "eagle-import:1206")
      (libsource (lib "eagle-import") (part "FUSE_(2)"))
    )
    (comp (ref "F3")
      (value "C1F 4")
      (footprint "eagle-import:1206")
      (libsource (lib "eagle-import") (part "FUSE_(2)"))
    )
    (comp (ref "F4")
      (value "C1F 4")
      (footprint "eagle-import:1206")
      (libsource (lib "eagle-import") (part "FUSE_(2)"))
    )
    (comp (ref "F5")
      (value "C1F 4")
      (footprint "eagle-import:1206")
      (libsource (lib "eagle-import") (part "FUSE_(2)"))
    )
    (comp (ref "F6")
      (value "C1F 3")
      (footprint "eagle-import:1206")
      (libsource (lib "eagle-import") (part "FUSE_(2)"))
    )
    (comp (ref "J1")
      (value "PIC_ICSP_5PIN")
      (footprint "eagle-import:SULLINS_XPXC_5PIN")
      (libsource (lib "eagle-import") (part "PIC_ICSP_5PIN"))
    )
    (comp (ref "J2")
      (value "68021-410HLF")
      (footprint "eagle-import:CON_100MIL_2X5")
      (libsource (lib "eagle-import") (part "CON_10PIN_(3)"))
    )
    (comp (ref "L1")
      (value "SRR1280-180M")
      (footprint "eagle-import:BOURNS_SRR1280")
      (libsource (lib "eagle-import") (part "INDUCTOR_(B6)"))
    )
    (comp (ref "L2")
      (value "MLZ2012M100WT000")
      (footprint "eagle-import:0805")
      (libsource (lib "eagle-import") (part "INDUCTOR_(3)"))
    )
    (comp (ref "L3")
      (value "SRR1280-180M")
      (footprint "eagle-import:BOURNS_SRR1280")
      (libsource (lib "eagle-import") (part "INDUCTOR_(B6)"))
    )
    (comp (ref "L4")
      (value "SRN1060-330M")
      (footprint "eagle-import:BOURNS_SRN1060")
      (libsource (lib "eagle-import") (part "INDUCTOR_(B1)"))
    )
    (comp (ref "L5")
      (value "SRN1060-180M")
      (footprint "eagle-import:BOURNS_SRN1060")
      (libsource (lib "eagle-import") (part "INDUCTOR_(B1)"))
    )
    (comp (ref "L6")
      (value "SRN1060-180M")
      (footprint "eagle-import:BOURNS_SRN1060")
      (libsource (lib "eagle-import") (part "INDUCTOR_(B1)"))
    )
    (comp (ref "P1")
      (value "SOLDER_PAD_(9)")
      (footprint "eagle-import:SOLDER_PAD_5X8")
      (libsource (lib "eagle-import") (part "SOLDER_PAD_(9)"))
    )
    (comp (ref "P2")
      (value "SOLDER_PAD_(9)")
      (footprint "eagle-import:SOLDER_PAD_5X8")
      (libsource (lib "eagle-import") (part "SOLDER_PAD_(9)"))
    )
    (comp (ref "P3")
      (value "SOLDER_PAD_(9)")
      (footprint "eagle-import:SOLDER_PAD_5X8")
      (libsource (lib "eagle-import") (part "SOLDER_PAD_(9)"))
    )
    (comp (ref "P4")
      (value "SOLDER_PAD_(9)")
      (footprint "eagle-import:SOLDER_PAD_5X8")
      (libsource (lib "eagle-import") (part "SOLDER_PAD_(9)"))
    )
    (comp (ref "P5")
      (value "SOLDER_PAD_(9)")
      (footprint "eagle-import:SOLDER_PAD_5X8")
      (libsource (lib "eagle-import") (part "SOLDER_PAD_(9)"))
    )
    (comp (ref "P6")
      (value "SOLDER_PAD_(9)")
      (footprint "eagle-import:SOLDER_PAD_5X8")
      (libsource (lib "eagle-import") (part "SOLDER_PAD_(9)"))
    )
    (comp (ref "P7")
      (value "SOLDER_PAD_(9)")
      (footprint "eagle-import:SOLDER_PAD_5X8")
      (libsource (lib "eagle-import") (part "SOLDER_PAD_(9)"))
    )
    (comp (ref "P8")
      (value "SOLDER_PAD_(9)")
      (footprint "eagle-import:SOLDER_PAD_5X8")
      (libsource (lib "eagle-import") (part "SOLDER_PAD_(9)"))
    )
    (comp (ref "P9")
      (value "SOLDER_PAD_(9)")
      (footprint "eagle-import:SOLDER_PAD_5X8")
      (libsource (lib "eagle-import") (part "SOLDER_PAD_(9)"))
    )
    (comp (ref "P10")
      (value "SOLDER_PAD_(9)")
      (footprint "eagle-import:SOLDER_PAD_5X8")
      (libsource (lib "eagle-import") (part "SOLDER_PAD_(9)"))
    )
    (comp (ref "P11")
      (value "SOLDER_PAD_(9)")
      (footprint "eagle-import:SOLDER_PAD_5X8")
      (libsource (lib "eagle-import") (part "SOLDER_PAD_(9)"))
    )
    (comp (ref "P12")
      (value "SOLDER_PAD_(9)")
      (footprint "eagle-import:SOLDER_PAD_5X8")
      (libsource (lib "eagle-import") (part "SOLDER_PAD_(9)"))
    )
    (comp (ref "Q1")
      (value "DMP3017SFG-7")
      (footprint "eagle-import:POWERVDFN-8")
      (libsource (lib "eagle-import") (part "PMOS_SSSGDDDD(3)"))
    )
    (comp (ref "Q2")
      (value "2N7002P")
      (footprint "eagle-import:SOT-23-3")
      (libsource (lib "eagle-import") (part "NMOS_GSD(1)"))
    )
    (comp (ref "Q3")
      (value "AON6980")
      (footprint "eagle-import:DFN5X6B_8L_EP2_ALPHA&OMEGA")
      (libsource (lib "eagle-import") (part "NMOS_HALFBRIDGE"))
    )
    (comp (ref "Q4")
      (value "DMP3017SFG-7")
      (footprint "eagle-import:POWERVDFN-8")
      (libsource (lib "eagle-import") (part "PMOS_SSSGDDDD(3)"))
    )
    (comp (ref "Q5")
      (value "2N7002P")
      (footprint "eagle-import:SOT-23-3")
      (libsource (lib "eagle-import") (part "NMOS_GSD(1)"))
    )
    (comp (ref "Q6")
      (value "DMP3017SFG-7")
      (footprint "eagle-import:POWERVDFN-8")
      (libsource (lib "eagle-import") (part "PMOS_SSSGDDDD(3)"))
    )
    (comp (ref "Q7")
      (value "AON6980")
      (footprint "eagle-import:DFN5X6B_8L_EP2_ALPHA&OMEGA")
      (libsource (lib "eagle-import") (part "NMOS_HALFBRIDGE"))
    )
    (comp (ref "Q8")
      (value "2N7002P")
      (footprint "eagle-import:SOT-23-3")
      (libsource (lib "eagle-import") (part "NMOS_GSD(1)"))
    )
    (comp (ref "Q9")
      (value "DMP3017SFG-7")
      (footprint "eagle-import:POWERVDFN-8")
      (libsource (lib "eagle-import") (part "PMOS_SSSGDDDD(3)"))
    )
    (comp (ref "Q10")
      (value "2N7002P")
      (footprint "eagle-import:SOT-23-3")
      (libsource (lib "eagle-import") (part "NMOS_GSD(1)"))
    )
    (comp (ref "Q11")
      (value "DMP3017SFG-7")
      (footprint "eagle-import:POWERVDFN-8")
      (libsource (lib "eagle-import") (part "PMOS_SSSGDDDD(3)"))
    )
    (comp (ref "Q12")
      (value "2N7002P")
      (footprint "eagle-import:SOT-23-3")
      (libsource (lib "eagle-import") (part "NMOS_GSD(1)"))
    )
    (comp (ref "Q13")
      (value "AON6980")
      (footprint "eagle-import:DFN5X6B_8L_EP2_ALPHA&OMEGA")
      (libsource (lib "eagle-import") (part "NMOS_HALFBRIDGE"))
    )
    (comp (ref "Q14")
      (value "DMP3017SFG-7")
      (footprint "eagle-import:POWERVDFN-8")
      (libsource (lib "eagle-import") (part "PMOS_SSSGDDDD(3)"))
    )
    (comp (ref "Q15")
      (value "2N7002P")
      (footprint "eagle-import:SOT-23-3")
      (libsource (lib "eagle-import") (part "NMOS_GSD(1)"))
    )
    (comp (ref "Q16")
      (value "AON6980")
      (footprint "eagle-import:DFN5X6B_8L_EP2_ALPHA&OMEGA")
      (libsource (lib "eagle-import") (part "NMOS_HALFBRIDGE"))
    )
    (comp (ref "Q17")
      (value "AON6980")
      (footprint "eagle-import:DFN5X6B_8L_EP2_ALPHA&OMEGA")
      (libsource (lib "eagle-import") (part "NMOS_HALFBRIDGE"))
    )
    (comp (ref "R1")
      (value "14.7k")
      (footprint "eagle-import:0805")
      (libsource (lib "eagle-import") (part "RESISTOR_(7)"))
    )
    (comp (ref "R2")
      (value "100k")
      (footprint "eagle-import:0805")
      (libsource (lib "eagle-import") (part "RESISTOR_(7)"))
    )
    (comp (ref "R3")
      (value "10k")
      (footprint "eagle-import:0805")
      (libsource (lib "eagle-import") (part "RESISTOR_(7)"))
    )
    (comp (ref "R4")
      (value "10mR")
      (footprint "eagle-import:0805")
      (libsource (lib "eagle-import") (part "RESISTOR_(7)"))
    )
    (comp (ref "R5")
      (value "2.2")
      (footprint "eagle-import:0805")
      (libsource (lib "eagle-import") (part "RESISTOR_(7)"))
    )
    (comp (ref "R6")
      (value "10k")
      (footprint "eagle-import:0805")
      (libsource (lib "eagle-import") (part "RESISTOR_(7)"))
    )
    (comp (ref "R7")
      (value "100k")
      (footprint "eagle-import:0805")
      (libsource (lib "eagle-import") (part "RESISTOR_(7)"))
    )
    (comp (ref "R8")
      (value "2k")
      (footprint "eagle-import:0805")
      (libsource (lib "eagle-import") (part "RESISTOR_(7)"))
    )
    (comp (ref "R9")
      (value "49.9k 1%")
      (footprint "eagle-import:0805")
      (libsource (lib "eagle-import") (part "RESISTOR_(7)"))
    )
    (comp (ref "R10")
      (value "100k")
      (footprint "eagle-import:0805")
      (libsource (lib "eagle-import") (part "RESISTOR_(7)"))
    )
    (comp (ref "R11")
      (value "10.5k")
      (footprint "eagle-import:0805")
      (libsource (lib "eagle-import") (part "RESISTOR_(7)"))
    )
    (comp (ref "R12")
      (value "1.82k 1%")
      (footprint "eagle-import:0805")
      (libsource (lib "eagle-import") (part "RESISTOR_(7)"))
    )
    (comp (ref "R13")
      (value "30")
      (footprint "eagle-import:0805")
      (libsource (lib "eagle-import") (part "RESISTOR_(7)"))
    )
    (comp (ref "R14")
      (value "14.7k")
      (footprint "eagle-import:0805")
      (libsource (lib "eagle-import") (part "RESISTOR_(7)"))
    )
    (comp (ref "R15")
      (value "100k")
      (footprint "eagle-import:0805")
      (libsource (lib "eagle-import") (part "RESISTOR_(7)"))
    )
    (comp (ref "R16")
      (value "10k")
      (footprint "eagle-import:0805")
      (libsource (lib "eagle-import") (part "RESISTOR_(7)"))
    )
    (comp (ref "R17")
      (value "10k")
      (footprint "eagle-import:0805")
      (libsource (lib "eagle-import") (part "RESISTOR_(7)"))
    )
    (comp (ref "R18")
      (value "10k")
      (footprint "eagle-import:0805")
      (libsource (lib "eagle-import") (part "RESISTOR_(7)"))
    )
    (comp (ref "R19")
      (value "100")
      (footprint "eagle-import:0805")
      (libsource (lib "eagle-import") (part "RESISTOR_(7)"))
    )
    (comp (ref "R20")
      (value "14.7k")
      (footprint "eagle-import:0805")
      (libsource (lib "eagle-import") (part "RESISTOR_(7)"))
    )
    (comp (ref "R21")
      (value "2.2")
      (footprint "eagle-import:0805")
      (libsource (lib "eagle-import") (part "RESISTOR_(7)"))
    )
    (comp (ref "R22")
      (value "49.9")
      (footprint "eagle-import:0805")
      (libsource (lib "eagle-import") (part "RESISTOR_(7)"))
    )
    (comp (ref "R23")
      (value "100k")
      (footprint "eagle-import:0805")
      (libsource (lib "eagle-import") (part "RESISTOR_(7)"))
    )
    (comp (ref "R24")
      (value "10k")
      (footprint "eagle-import:0805")
      (libsource (lib "eagle-import") (part "RESISTOR_(7)"))
    )
    (comp (ref "R25")
      (value "49.9")
      (footprint "eagle-import:0805")
      (libsource (lib "eagle-import") (part "RESISTOR_(7)"))
    )
    (comp (ref "R26")
      (value "10mR")
      (footprint "eagle-import:0805")
      (libsource (lib "eagle-import") (part "RESISTOR_(7)"))
    )
    (comp (ref "R27")
      (value "2k")
      (footprint "eagle-import:0805")
      (libsource (lib "eagle-import") (part "RESISTOR_(7)"))
    )
    (comp (ref "R28")
      (value "49.9k 1%")
      (footprint "eagle-import:0805")
      (libsource (lib "eagle-import") (part "RESISTOR_(7)"))
    )
    (comp (ref "R29")
      (value "10k")
      (footprint "eagle-import:0805")
      (libsource (lib "eagle-import") (part "RESISTOR_(7)"))
    )
    (comp (ref "R30")
      (value "100k")
      (footprint "eagle-import:0805")
      (libsource (lib "eagle-import") (part "RESISTOR_(7)"))
    )
    (comp (ref "R31")
      (value "43k")
      (footprint "eagle-import:0805")
      (libsource (lib "eagle-import") (part "RESISTOR_(7)"))
    )
    (comp (ref "R32")
      (value "10.5k")
      (footprint "eagle-import:0805")
      (libsource (lib "eagle-import") (part "RESISTOR_(7)"))
    )
    (comp (ref "R33")
      (value "1.82k 1%")
      (footprint "eagle-import:0805")
      (libsource (lib "eagle-import") (part "RESISTOR_(7)"))
    )
    (comp (ref "R34")
      (value "30")
      (footprint "eagle-import:0805")
      (libsource (lib "eagle-import") (part "RESISTOR_(7)"))
    )
    (comp (ref "R35")
      (value "43k")
      (footprint "eagle-import:0805")
      (libsource (lib "eagle-import") (part "RESISTOR_(7)"))
    )
    (comp (ref "R36")
      (value "15k 1%")
      (footprint "eagle-import:0805")
      (libsource (lib "eagle-import") (part "RESISTOR_(7)"))
    )
    (comp (ref "R37")
      (value "4.99k 1%")
      (footprint "eagle-import:0805")
      (libsource (lib "eagle-import") (part "RESISTOR_(7)"))
    )
    (comp (ref "R38")
      (value "14.7k")
      (footprint "eagle-import:0805")
      (libsource (lib "eagle-import") (part "RESISTOR_(7)"))
    )
    (comp (ref "R39")
      (value "100k")
      (footprint "eagle-import:0805")
      (libsource (lib "eagle-import") (part "RESISTOR_(7)"))
    )
    (comp (ref "R40")
      (value "10k")
      (footprint "eagle-import:0805")
      (libsource (lib "eagle-import") (part "RESISTOR_(7)"))
    )
    (comp (ref "R41")
      (value "10k")
      (footprint "eagle-import:0805")
      (libsource (lib "eagle-import") (part "RESISTOR_(7)"))
    )
    (comp (ref "R42")
      (value "14.7k")
      (footprint "eagle-import:0805")
      (libsource (lib "eagle-import") (part "RESISTOR_(7)"))
    )
    (comp (ref "R43")
      (value "10k")
      (footprint "eagle-import:0805")
      (libsource (lib "eagle-import") (part "RESISTOR_(7)"))
    )
    (comp (ref "R44")
      (value "10mR")
      (footprint "eagle-import:0805")
      (libsource (lib "eagle-import") (part "RESISTOR_(7)"))
    )
    (comp (ref "R45")
      (value "10k")
      (footprint "eagle-import:0805")
      (libsource (lib "eagle-import") (part "RESISTOR_(7)"))
    )
    (comp (ref "R46")
      (value "2.2")
      (footprint "eagle-import:0805")
      (libsource (lib "eagle-import") (part "RESISTOR_(7)"))
    )
    (comp (ref "R47")
      (value "2.2")
      (footprint "eagle-import:0805")
      (libsource (lib "eagle-import") (part "RESISTOR_(7)"))
    )
    (comp (ref "R48")
      (value "49.9k 1%")
      (footprint "eagle-import:0805")
      (libsource (lib "eagle-import") (part "RESISTOR_(7)"))
    )
    (comp (ref "R49")
      (value "3.9k 1%")
      (footprint "eagle-import:0805")
      (libsource (lib "eagle-import") (part "RESISTOR_(7)"))
    )
    (comp (ref "R50")
      (value "1.62k")
      (footprint "eagle-import:0805")
      (libsource (lib "eagle-import") (part "RESISTOR_(7)"))
    )
    (comp (ref "R51")
      (value "1.43k")
      (footprint "eagle-import:0805")
      (libsource (lib "eagle-import") (part "RESISTOR_(7)"))
    )
    (comp (ref "R52")
      (value "49.9k 1%")
      (footprint "eagle-import:0805")
      (libsource (lib "eagle-import") (part "RESISTOR_(7)"))
    )
    (comp (ref "R53")
      (value "10k")
      (footprint "eagle-import:0805")
      (libsource (lib "eagle-import") (part "RESISTOR_(7)"))
    )
    (comp (ref "R54")
      (value "15k 1%")
      (footprint "eagle-import:0805")
      (libsource (lib "eagle-import") (part "RESISTOR_(7)"))
    )
    (comp (ref "R55")
      (value "7.5k")
      (footprint "eagle-import:0805")
      (libsource (lib "eagle-import") (part "RESISTOR_(7)"))
    )
    (comp (ref "R56")
      (value "10.5k")
      (footprint "eagle-import:0805")
      (libsource (lib "eagle-import") (part "RESISTOR_(7)"))
    )
    (comp (ref "R57")
      (value "6.81k 1%")
      (footprint "eagle-import:0805")
      (libsource (lib "eagle-import") (part "RESISTOR_(7)"))
    )
    (comp (ref "R58")
      (value "14.7k")
      (footprint "eagle-import:0805")
      (libsource (lib "eagle-import") (part "RESISTOR_(7)"))
    )
    (comp (ref "R59")
      (value "100k")
      (footprint "eagle-import:0805")
      (libsource (lib "eagle-import") (part "RESISTOR_(7)"))
    )
    (comp (ref "R60")
      (value "10k")
      (footprint "eagle-import:0805")
      (libsource (lib "eagle-import") (part "RESISTOR_(7)"))
    )
    (comp (ref "R61")
      (value "10mR")
      (footprint "eagle-import:0805")
      (libsource (lib "eagle-import") (part "RESISTOR_(7)"))
    )
    (comp (ref "R62")
      (value "2.2")
      (footprint "eagle-import:0805")
      (libsource (lib "eagle-import") (part "RESISTOR_(7)"))
    )
    (comp (ref "R63")
      (value "10k")
      (footprint "eagle-import:0805")
      (libsource (lib "eagle-import") (part "RESISTOR_(7)"))
    )
    (comp (ref "R64")
      (value "1.62k")
      (footprint "eagle-import:0805")
      (libsource (lib "eagle-import") (part "RESISTOR_(7)"))
    )
    (comp (ref "R65")
      (value "49.9k 1%")
      (footprint "eagle-import:0805")
      (libsource (lib "eagle-import") (part "RESISTOR_(7)"))
    )
    (comp (ref "R66")
      (value "10k")
      (footprint "eagle-import:0805")
      (libsource (lib "eagle-import") (part "RESISTOR_(7)"))
    )
    (comp (ref "R67")
      (value "4.99k 1%")
      (footprint "eagle-import:0805")
      (libsource (lib "eagle-import") (part "RESISTOR_(7)"))
    )
    (comp (ref "R68")
      (value "300")
      (footprint "eagle-import:0805")
      (libsource (lib "eagle-import") (part "RESISTOR_(7)"))
    )
    (comp (ref "R69")
      (value "10.5k")
      (footprint "eagle-import:0805")
      (libsource (lib "eagle-import") (part "RESISTOR_(7)"))
    )
    (comp (ref "R70")
      (value "6.81k 1%")
      (footprint "eagle-import:0805")
      (libsource (lib "eagle-import") (part "RESISTOR_(7)"))
    )
    (comp (ref "R71")
      (value "10k")
      (footprint "eagle-import:0805")
      (libsource (lib "eagle-import") (part "RESISTOR_(7)"))
    )
    (comp (ref "R72")
      (value "10k 1%")
      (footprint "eagle-import:0805")
      (libsource (lib "eagle-import") (part "RESISTOR_(7)"))
    )
    (comp (ref "R73")
      (value "10k 1%")
      (footprint "eagle-import:0805")
      (libsource (lib "eagle-import") (part "RESISTOR_(7)"))
    )
    (comp (ref "R74")
      (value "15k 1%")
      (footprint "eagle-import:0805")
      (libsource (lib "eagle-import") (part "RESISTOR_(7)"))
    )
    (comp (ref "R75")
      (value "4.99k 1%")
      (footprint "eagle-import:0805")
      (libsource (lib "eagle-import") (part "RESISTOR_(7)"))
    )
    (comp (ref "R76")
      (value "15k 1%")
      (footprint "eagle-import:0805")
      (libsource (lib "eagle-import") (part "RESISTOR_(7)"))
    )
    (comp (ref "R77")
      (value "4.99k 1%")
      (footprint "eagle-import:0805")
      (libsource (lib "eagle-import") (part "RESISTOR_(7)"))
    )
    (comp (ref "R78")
      (value "49.9")
      (footprint "eagle-import:0805")
      (libsource (lib "eagle-import") (part "RESISTOR_(7)"))
    )
    (comp (ref "R79")
      (value "10mR")
      (footprint "eagle-import:0805")
      (libsource (lib "eagle-import") (part "RESISTOR_(7)"))
    )
    (comp (ref "R80")
      (value "100k")
      (footprint "eagle-import:0805")
      (libsource (lib "eagle-import") (part "RESISTOR_(7)"))
    )
    (comp (ref "R81")
      (value "49.9")
      (footprint "eagle-import:0805")
      (libsource (lib "eagle-import") (part "RESISTOR_(7)"))
    )
    (comp (ref "U1")
      (value "CS30CL")
      (footprint "eagle-import:SOT-23-5")
      (libsource (lib "eagle-import") (part "CS30"))
    )
    (comp (ref "U2")
      (value "MCP19035-AAABE/MF")
      (footprint "eagle-import:VFDFN-10_EP")
      (libsource (lib "eagle-import") (part "MCP19035"))
    )
    (comp (ref "U3")
      (value "PIC16F1773-I/SS")
      (footprint "eagle-import:SSOP-28")
      (libsource (lib "eagle-import") (part "16F1773/6/7/8/9"))
    )
    (comp (ref "U4")
      (value "CS30CL")
      (footprint "eagle-import:SOT-23-5")
      (libsource (lib "eagle-import") (part "CS30"))
    )
    (comp (ref "U5")
      (value "MCP19035-AAABE/MF")
      (footprint "eagle-import:VFDFN-10_EP")
      (libsource (lib "eagle-import") (part "MCP19035"))
    )
    (comp (ref "U6")
      (value "CS30CL")
      (footprint "eagle-import:SOT-23-5")
      (libsource (lib "eagle-import") (part "CS30"))
    )
    (comp (ref "U7")
      (value "MCP19035-AAABE/MF")
      (footprint "eagle-import:VFDFN-10_EP")
      (libsource (lib "eagle-import") (part "MCP19035"))
    )
    (comp (ref "U8")
      (value "MCP19035-AAABE/MF")
      (footprint "eagle-import:VFDFN-10_EP")
      (libsource (lib "eagle-import") (part "MCP19035"))
    )
    (comp (ref "U9")
      (value "CS30CL")
      (footprint "eagle-import:SOT-23-5")
      (libsource (lib "eagle-import") (part "CS30"))
    )
    (comp (ref "U10")
      (value "MCP19035-AAABE/MF")
      (footprint "eagle-import:VFDFN-10_EP")
      (libsource (lib "eagle-import") (part "MCP19035"))
    )
    (comp (ref "U11")
      (value "MC78M12CDTG")
      (footprint "eagle-import:TO-252-3")
      (libsource (lib "eagle-import") (part "LDO_IOG"))
    )
    (comp (ref "U12")
      (value "MCP6L01UT-E/OT")
      (footprint "eagle-import:SOT-23-5")
      (libsource (lib "eagle-import") (part "OP-AMP_MCP6L01U"))
    )
    (comp (ref "U13")
      (value "MCP6L01UT-E/OT")
      (footprint "eagle-import:SOT-23-5")
      (libsource (lib "eagle-import") (part "OP-AMP_MCP6L01U"))
    )
    (comp (ref "U14")
      (value "MC78M05CDTG")
      (footprint "eagle-import:TO-252-3")
      (libsource (lib "eagle-import") (part "LDO_IOG"))
    )
    (comp (ref "U15")
      (value "CS30CL")
      (footprint "eagle-import:SOT-23-5")
      (libsource (lib "eagle-import") (part "CS30"))
    )
    (comp (ref "U16")
      (value "MCP6L01UT-E/OT")
      (footprint "eagle-import:SOT-23-5")
      (libsource (lib "eagle-import") (part "OP-AMP_MCP6L01U"))
    )
  )
  (nets
    (net (code "1") (name "+8.3V") (class "Default")
      (node (ref "D9") (pin "C") (pinfunction "C_C") (pintype "passive"))
      (node (ref "F6") (pin "1") (pinfunction "1_1") (pintype "bidirectional"))
      (node (ref "P9") (pin "1") (pinfunction "P$1_1") (pintype "bidirectional"))
      (node (ref "R72") (pin "2") (pinfunction "2_2") (pintype "passive"))
    )
    (net (code "2") (name "+16.8(1)V") (class "Default")
      (node (ref "C10") (pin "1") (pinfunction "1_1") (pintype "passive"))
      (node (ref "C11") (pin "1") (pinfunction "1_1") (pintype "passive"))
      (node (ref "C13") (pin "1") (pinfunction "1_1") (pintype "passive"))
      (node (ref "C14") (pin "1") (pinfunction "1_1") (pintype "passive"))
      (node (ref "C15") (pin "1") (pinfunction "1_1") (pintype "passive"))
      (node (ref "C18") (pin "1") (pinfunction "1_1") (pintype "passive"))
      (node (ref "C2") (pin "1") (pinfunction "1_1") (pintype "passive"))
      (node (ref "C39") (pin "1") (pinfunction "1_1") (pintype "passive"))
      (node (ref "C9") (pin "1") (pinfunction "1_1") (pintype "passive"))
      (node (ref "L1") (pin "P$2") (pinfunction "2_P$2") (pintype "passive"))
      (node (ref "Q1") (pin "1") (pinfunction "S_1") (pintype "bidirectional"))
      (node (ref "Q1") (pin "2") (pinfunction "S_2") (pintype "bidirectional"))
      (node (ref "Q1") (pin "3") (pinfunction "S_3") (pintype "bidirectional"))
      (node (ref "Q4") (pin "1") (pinfunction "S_1") (pintype "bidirectional"))
      (node (ref "Q4") (pin "2") (pinfunction "S_2") (pintype "bidirectional"))
      (node (ref "Q4") (pin "3") (pinfunction "S_3") (pintype "bidirectional"))
      (node (ref "Q9") (pin "1") (pinfunction "S_1") (pintype "bidirectional"))
      (node (ref "Q9") (pin "2") (pinfunction "S_2") (pintype "bidirectional"))
      (node (ref "Q9") (pin "3") (pinfunction "S_3") (pintype "bidirectional"))
      (node (ref "R1") (pin "2") (pinfunction "2_2") (pintype "passive"))
      (node (ref "R14") (pin "2") (pinfunction "2_2") (pintype "passive"))
      (node (ref "R38") (pin "2") (pinfunction "2_2") (pintype "passive"))
      (node (ref "R8") (pin "2") (pinfunction "2_2") (pintype "passive"))
      (node (ref "R9") (pin "2") (pinfunction "2_2") (pintype "passive"))
    )
    (net (code "3") (name "+16.8(2)V") (class "Default")
      (node (ref "C25") (pin "1") (pinfunction "1_1") (pintype "passive"))
      (node (ref "C30") (pin "1") (pinfunction "1_1") (pintype "passive"))
      (node (ref "C31") (pin "1") (pinfunction "1_1") (pintype "passive"))
      (node (ref "C32") (pin "1") (pinfunction "1_1") (pintype "passive"))
      (node (ref "C34") (pin "1") (pinfunction "1_1") (pintype "passive"))
      (node (ref "C35") (pin "1") (pinfunction "1_1") (pintype "passive"))
      (node (ref "C36") (pin "1") (pinfunction "1_1") (pintype "passive"))
      (node (ref "C41") (pin "1") (pinfunction "1_1") (pintype "passive"))
      (node (ref "C67") (pin "1") (pinfunction "1_1") (pintype "passive"))
      (node (ref "L3") (pin "P$2") (pinfunction "2_P$2") (pintype "passive"))
      (node (ref "Q11") (pin "1") (pinfunction "S_1") (pintype "bidirectional"))
      (node (ref "Q11") (pin "2") (pinfunction "S_2") (pintype "bidirectional"))
      (node (ref "Q11") (pin "3") (pinfunction "S_3") (pintype "bidirectional"))
      (node (ref "Q14") (pin "1") (pinfunction "S_1") (pintype "bidirectional"))
      (node (ref "Q14") (pin "2") (pinfunction "S_2") (pintype "bidirectional"))
      (node (ref "Q14") (pin "3") (pinfunction "S_3") (pintype "bidirectional"))
      (node (ref "Q6") (pin "1") (pinfunction "S_1") (pintype "bidirectional"))
      (node (ref "Q6") (pin "2") (pinfunction "S_2") (pintype "bidirectional"))
      (node (ref "Q6") (pin "3") (pinfunction "S_3") (pintype "bidirectional"))
      (node (ref "R20") (pin "2") (pinfunction "2_2") (pintype "passive"))
      (node (ref "R27") (pin "2") (pinfunction "2_2") (pintype "passive"))
      (node (ref "R28") (pin "2") (pinfunction "2_2") (pintype "passive"))
      (node (ref "R42") (pin "2") (pinfunction "2_2") (pintype "passive"))
      (node (ref "R58") (pin "2") (pinfunction "2_2") (pintype "passive"))
    )
    (net (code "4") (name "+24V") (class "Default")
      (node (ref "C21") (pin "1") (pinfunction "1_1") (pintype "passive"))
      (node (ref "C22") (pin "1") (pinfunction "1_1") (pintype "passive"))
      (node (ref "C26") (pin "1") (pinfunction "1_1") (pintype "passive"))
      (node (ref "C27") (pin "1") (pinfunction "1_1") (pintype "passive"))
      (node (ref "C3") (pin "1") (pinfunction "1_1") (pintype "passive"))
      (node (ref "C4") (pin "1") (pinfunction "1_1") (pintype "passive"))
      (node (ref "C42") (pin "1") (pinfunction "1_1") (pintype "passive"))
      (node (ref "C43") (pin "1") (pinfunction "1_1") (pintype "passive"))
      (node (ref "C45") (pin "1") (pinfunction "1_1") (pintype "passive"))
      (node (ref "C46") (pin "1") (pinfunction "1_1") (pintype "passive"))
      (node (ref "C47") (pin "1") (pinfunction "1_1") (pintype "passive"))
      (node (ref "C5") (pin "1") (pinfunction "1_1") (pintype "passive"))
      (node (ref "C50") (pin "1") (pinfunction "1_1") (pintype "passive"))
      (node (ref "C51") (pin "1") (pinfunction "1_1") (pintype "passive"))
      (node (ref "C6") (pin "1") (pinfunction "1_1") (pintype "passive"))
      (node (ref "C68") (pin "1") (pinfunction "1_1") (pintype "passive"))
      (node (ref "C69") (pin "1") (pinfunction "1_1") (pintype "passive"))
      (node (ref "C70") (pin "1") (pinfunction "1_1") (pintype "passive"))
      (node (ref "C71") (pin "1") (pinfunction "1_1") (pintype "passive"))
      (node (ref "C81") (pin "1") (pinfunction "1_1") (pintype "passive"))
      (node (ref "C82") (pin "1") (pinfunction "1_1") (pintype "passive"))
      (node (ref "F1") (pin "2") (pinfunction "2_2") (pintype "bidirectional"))
      (node (ref "Q13") (pin "2") (pinfunction "D1_2") (pintype "bidirectional"))
      (node (ref "Q13") (pin "3") (pinfunction "D1_3") (pintype "bidirectional"))
      (node (ref "Q13") (pin "4") (pinfunction "D1_4") (pintype "bidirectional"))
      (node (ref "Q13") (pin "EP1@1") (pinfunction "D1_EP1@1") (pintype "bidirectional"))
      (node (ref "Q13") (pin "EP1@2") (pinfunction "D1_EP1@2") (pintype "bidirectional"))
      (node (ref "Q16") (pin "2") (pinfunction "D1_2") (pintype "bidirectional"))
      (node (ref "Q16") (pin "3") (pinfunction "D1_3") (pintype "bidirectional"))
      (node (ref "Q16") (pin "4") (pinfunction "D1_4") (pintype "bidirectional"))
      (node (ref "Q16") (pin "EP1@1") (pinfunction "D1_EP1@1") (pintype "bidirectional"))
      (node (ref "Q16") (pin "EP1@2") (pinfunction "D1_EP1@2") (pintype "bidirectional"))
      (node (ref "Q17") (pin "2") (pinfunction "D1_2") (pintype "bidirectional"))
      (node (ref "Q17") (pin "3") (pinfunction "D1_3") (pintype "bidirectional"))
      (node (ref "Q17") (pin "4") (pinfunction "D1_4") (pintype "bidirectional"))
      (node (ref "Q17") (pin "EP1@1") (pinfunction "D1_EP1@1") (pintype "bidirectional"))
      (node (ref "Q17") (pin "EP1@2") (pinfunction "D1_EP1@2") (pintype "bidirectional"))
      (node (ref "Q3") (pin "2") (pinfunction "D1_2") (pintype "bidirectional"))
      (node (ref "Q3") (pin "3") (pinfunction "D1_3") (pintype "bidirectional"))
      (node (ref "Q3") (pin "4") (pinfunction "D1_4") (pintype "bidirectional"))
      (node (ref "Q3") (pin "EP1@1") (pinfunction "D1_EP1@1") (pintype "bidirectional"))
      (node (ref "Q3") (pin "EP1@2") (pinfunction "D1_EP1@2") (pintype "bidirectional"))
      (node (ref "Q7") (pin "2") (pinfunction "D1_2") (pintype "bidirectional"))
      (node (ref "Q7") (pin "3") (pinfunction "D1_3") (pintype "bidirectional"))
      (node (ref "Q7") (pin "4") (pinfunction "D1_4") (pintype "bidirectional"))
      (node (ref "Q7") (pin "EP1@1") (pinfunction "D1_EP1@1") (pintype "bidirectional"))
      (node (ref "Q7") (pin "EP1@2") (pinfunction "D1_EP1@2") (pintype "bidirectional"))
      (node (ref "R21") (pin "1") (pinfunction "1_1") (pintype "passive"))
      (node (ref "R46") (pin "1") (pinfunction "1_1") (pintype "passive"))
      (node (ref "R47") (pin "1") (pinfunction "1_1") (pintype "passive"))
      (node (ref "R5") (pin "1") (pinfunction "1_1") (pintype "passive"))
      (node (ref "R62") (pin "1") (pinfunction "1_1") (pintype "passive"))
      (node (ref "U11") (pin "1") (pinfunction "VIN_1") (pintype "bidirectional"))
    )
    (net (code "5") (name "/BATT1") (class "Default")
      (node (ref "D1") (pin "C") (pinfunction "C_C") (pintype "passive"))
      (node (ref "F2") (pin "1") (pinfunction "1_1") (pintype "bidirectional"))
      (node (ref "P2") (pin "1") (pinfunction "P$1_1") (pintype "bidirectional"))
      (node (ref "R36") (pin "2") (pinfunction "2_2") (pintype "passive"))
    )
    (net (code "6") (name "/BATT1_CURR_SENSE") (class "Default")
      (node (ref "U1") (pin "1") (pinfunction "VOUT_1") (pintype "bidirectional"))
      (node (ref "U3") (pin "13") (pinfunction "RC2/AN14/C[5,6]IN2-/T5CKI/IOCC2_13") (pintype "bidirectional"))
    )
    (net (code "7") (name "/BATT1_SRC1") (class "Default")
      (node (ref "Q2") (pin "1") (pinfunction "G_1") (pintype "bidirectional"))
      (node (ref "R6") (pin "2") (pinfunction "2_2") (pintype "passive"))
      (node (ref "U3") (pin "9") (pinfunction "RA7/CLKIN/OSC1/IOCA7_9") (pintype "bidirectional"))
    )
    (net (code "8") (name "/BATT1_V_SENSE") (class "Default")
      (node (ref "C102") (pin "1") (pinfunction "1_1") (pintype "passive"))
      (node (ref "R36") (pin "1") (pinfunction "1_1") (pintype "passive"))
      (node (ref "R37") (pin "2") (pinfunction "2_2") (pintype "passive"))
      (node (ref "U3") (pin "23") (pinfunction "RB2/AN8/OPAIN0-/DAC3OUT1/IOCB2_23") (pintype "bidirectional"))
    )
    (net (code "9") (name "/BATT2") (class "Default")
      (node (ref "D4") (pin "C") (pinfunction "C_C") (pintype "passive"))
      (node (ref "F3") (pin "1") (pinfunction "1_1") (pintype "bidirectional"))
      (node (ref "P6") (pin "1") (pinfunction "P$1_1") (pintype "bidirectional"))
      (node (ref "R54") (pin "2") (pinfunction "2_2") (pintype "passive"))
    )
    (net (code "10") (name "/BATT2_CURR_SENSE") (class "Default")
      (node (ref "U3") (pin "14") (pinfunction "RC3/AN15/C[5,6]IN2-/T5CKI/IOCC2_14") (pintype "bidirectional"))
      (node (ref "U4") (pin "1") (pinfunction "VOUT_1") (pintype "bidirectional"))
    )
    (net (code "11") (name "/BATT2_SRC1") (class "Default")
      (node (ref "Q5") (pin "1") (pinfunction "G_1") (pintype "bidirectional"))
      (node (ref "R17") (pin "2") (pinfunction "2_2") (pintype "passive"))
      (node (ref "U3") (pin "10") (pinfunction "RA6/CLKOUT/C6IN1+/OSC2/IOCA6_10") (pintype "bidirectional"))
    )
    (net (code "12") (name "/BATT2_SRC2") (class "Default")
      (node (ref "Q8") (pin "1") (pinfunction "G_1") (pintype "bidirectional"))
      (node (ref "R29") (pin "2") (pinfunction "2_2") (pintype "passive"))
      (node (ref "U3") (pin "12") (pinfunction "RC1/DAC7OUT1/IOCC1_12") (pintype "bidirectional"))
    )
    (net (code "13") (name "/BATT2_V_SENSE") (class "Default")
      (node (ref "C103") (pin "1") (pinfunction "1_1") (pintype "passive"))
      (node (ref "R54") (pin "1") (pinfunction "1_1") (pintype "passive"))
      (node (ref "R67") (pin "2") (pinfunction "2_2") (pintype "passive"))
      (node (ref "U3") (pin "22") (pinfunction "RB1/AN10/PRG1IN[0,1]/HIB1/C[1-4]IN3-/OPA2OUT/OPAIN1[+,-]/IOCB1_22") (pintype "bidirectional"))
    )
    (net (code "14") (name "/BATT3") (class "Default")
      (node (ref "D8") (pin "C") (pinfunction "C_C") (pintype "passive"))
      (node (ref "F4") (pin "1") (pinfunction "1_1") (pintype "bidirectional"))
      (node (ref "P8") (pin "1") (pinfunction "P$1_1") (pintype "bidirectional"))
      (node (ref "R74") (pin "2") (pinfunction "2_2") (pintype "passive"))
    )
    (net (code "15") (name "/BATT3_CURR_SENSE") (class "Default")
      (node (ref "U3") (pin "3") (pinfunction "RA1/AN1/PRG1IN0/IOCA1/C[1-4]IN1-_3") (pintype "bidirectional"))
      (node (ref "U6") (pin "1") (pinfunction "VOUT_1") (pintype "bidirectional"))
    )
    (net (code "16") (name "/BATT3_SRC1") (class "Default")
      (node (ref "Q10") (pin "1") (pinfunction "G_1") (pintype "bidirectional"))
      (node (ref "R41") (pin "2") (pinfunction "2_2") (pintype "passive"))
      (node (ref "U3") (pin "6") (pinfunction "RA4/OPA1IN0+/DAC4OUT1/T0CKI/IOCA4_6") (pintype "bidirectional"))
    )
    (net (code "17") (name "/BATT3_SRC2") (class "Default")
      (node (ref "Q12") (pin "1") (pinfunction "G_1") (pintype "bidirectional"))
      (node (ref "R45") (pin "2") (pinfunction "2_2") (pintype "passive"))
      (node (ref "U3") (pin "5") (pinfunction "RA3/AN3/VREF+/DAC[1-7]REF0+/C1IN1+/IOCA3_5") (pintype "bidirectional"))
    )
    (net (code "18") (name "/BATT3_V_SENSE") (class "Default")
      (node (ref "C104") (pin "1") (pinfunction "1_1") (pintype "passive"))
      (node (ref "R74") (pin "1") (pinfunction "1_1") (pintype "passive"))
      (node (ref "R75") (pin "2") (pinfunction "2_2") (pintype "passive"))
      (node (ref "U3") (pin "25") (pinfunction "RB4/AN11/C3IN1+/T5G/IOCB4_25") (pintype "bidirectional"))
    )
    (net (code "19") (name "/BATT4") (class "Default")
      (node (ref "D12") (pin "C") (pinfunction "C_C") (pintype "passive"))
      (node (ref "F5") (pin "1") (pinfunction "1_1") (pintype "bidirectional"))
      (node (ref "P12") (pin "1") (pinfunction "P$1_1") (pintype "bidirectional"))
      (node (ref "R76") (pin "2") (pinfunction "2_2") (pintype "passive"))
    )
    (net (code "20") (name "/BATT4_CURR_SENSE") (class "Default")
      (node (ref "U3") (pin "2") (pinfunction "RA0/AN0/IOCA0/C[1-6]IN0-_2") (pintype "bidirectional"))
      (node (ref "U9") (pin "1") (pinfunction "VOUT_1") (pintype "bidirectional"))
    )
    (net (code "21") (name "/BATT4_SRC2") (class "Default")
      (node (ref "Q15") (pin "1") (pinfunction "G_1") (pintype "bidirectional"))
      (node (ref "R63") (pin "2") (pinfunction "2_2") (pintype "passive"))
      (node (ref "U3") (pin "26") (pinfunction "RB5/AN13/DAC[5,7]REF1-/C4IN2-/T1G/IOCB5_26") (pintype "bidirectional"))
    )
    (net (code "22") (name "/BATT4_V_SENSE") (class "Default")
      (node (ref "C105") (pin "1") (pinfunction "1_1") (pintype "passive"))
      (node (ref "R76") (pin "1") (pinfunction "1_1") (pintype "passive"))
      (node (ref "R77") (pin "2") (pinfunction "2_2") (pintype "passive"))
      (node (ref "U3") (pin "24") (pinfunction "RB3/AN9/C[1-3]IN2-/OPA2IN0+/IOCB3_24") (pintype "bidirectional"))
    )
    (net (code "23") (name "/CONTROLLER_ADJ_DAC") (class "Default")
      (node (ref "C109") (pin "1") (pinfunction "1_1") (pintype "passive"))
      (node (ref "U16") (pin "1") (pinfunction "IN+_1") (pintype "input"))
      (node (ref "U3") (pin "11") (pinfunction "RC0/DAC5OUT1/T1CKI/T3CKI/T3G/IOCC0_11") (pintype "bidirectional"))
    )
    (net (code "24") (name "/CONTROLLER_CURR_SENSE") (class "Default")
      (node (ref "U15") (pin "1") (pinfunction "VOUT_1") (pintype "bidirectional"))
      (node (ref "U3") (pin "18") (pinfunction "RC7/AN19/OPA3IN0-/IOCC7_18") (pintype "bidirectional"))
    )
    (net (code "25") (name "/CONTROLLER_EN") (class "Default")
      (node (ref "R71") (pin "2") (pinfunction "2_2") (pintype "passive"))
      (node (ref "U3") (pin "15") (pinfunction "RC4/AN16/C[5,6]IN3-/T8IN/IOCC4_15") (pintype "bidirectional"))
      (node (ref "U7") (pin "1") (pinfunction "~{SHDN}_1") (pintype "bidirectional"))
    )
    (net (code "26") (name "/CONTROLLER_V_SENSE") (class "Default")
      (node (ref "C44") (pin "1") (pinfunction "1_1") (pintype "passive"))
      (node (ref "R72") (pin "1") (pinfunction "1_1") (pintype "passive"))
      (node (ref "R73") (pin "2") (pinfunction "2_2") (pintype "passive"))
      (node (ref "U3") (pin "21") (pinfunction "RB0/AN12/ZCD/HIB0/C2IN1+/IOCB0_21") (pintype "bidirectional"))
    )
    (net (code "27") (name "/PGC") (class "Default")
      (node (ref "J1") (pin "5") (pinfunction "ICSPCLK_5") (pintype "bidirectional"))
      (node (ref "R22") (pin "2") (pinfunction "2_2") (pintype "passive"))
    )
    (net (code "28") (name "/PGD") (class "Default")
      (node (ref "J1") (pin "4") (pinfunction "ICSPDAT_4") (pintype "bidirectional"))
      (node (ref "R25") (pin "2") (pinfunction "2_2") (pintype "passive"))
    )
    (net (code "29") (name "/USB1_EN") (class "Default")
      (node (ref "R53") (pin "2") (pinfunction "2_2") (pintype "passive"))
      (node (ref "U3") (pin "17") (pinfunction "RC6/AN18/PRG3IN0/C[5,6]IN1-/OPA3OUT/IOCC6_17") (pintype "bidirectional"))
      (node (ref "U8") (pin "1") (pinfunction "~{SHDN}_1") (pintype "bidirectional"))
    )
    (net (code "30") (name "/USB2_EN") (class "Default")
      (node (ref "R66") (pin "2") (pinfunction "2_2") (pintype "passive"))
      (node (ref "U10") (pin "1") (pinfunction "~{SHDN}_1") (pintype "bidirectional"))
      (node (ref "U3") (pin "16") (pinfunction "RC5/AN17/OPA3IN0+/T4IN/IOCC5_16") (pintype "bidirectional"))
    )
    (net (code "31") (name "/V1_ADJ_DAC") (class "Default")
      (node (ref "C98") (pin "1") (pinfunction "1_1") (pintype "passive"))
      (node (ref "U12") (pin "1") (pinfunction "IN+_1") (pintype "input"))
      (node (ref "U3") (pin "7") (pinfunction "RA5/AN4/OPA1IN0-/DAC2OUT1/IOCA5_7") (pintype "bidirectional"))
    )
    (net (code "32") (name "/V2_ADJ_DAC") (class "Default")
      (node (ref "C101") (pin "1") (pinfunction "1_1") (pintype "passive"))
      (node (ref "U13") (pin "1") (pinfunction "IN+_1") (pintype "input"))
      (node (ref "U3") (pin "4") (pinfunction "RA2/AN2/VREF-/DAC[1-7]REF0-/DAC1OUT1/IOCA2_4") (pintype "bidirectional"))
    )
    (net (code "33") (name "/~{MCLR}") (class "Default")
      (node (ref "C24") (pin "1") (pinfunction "1_1") (pintype "passive"))
      (node (ref "J1") (pin "1") (pinfunction "~{MCLR}_1") (pintype "bidirectional"))
      (node (ref "R18") (pin "1") (pinfunction "1_1") (pintype "passive"))
      (node (ref "R19") (pin "1") (pinfunction "1_1") (pintype "passive"))
    )
    (net (code "34") (name "5V") (class "Default")
      (node (ref "C1") (pin "1") (pinfunction "1_1") (pintype "passive"))
      (node (ref "C100") (pin "1") (pinfunction "1_1") (pintype "passive"))
      (node (ref "C108") (pin "1") (pinfunction "1_1") (pintype "passive"))
      (node (ref "C23") (pin "1") (pinfunction "1_1") (pintype "passive"))
      (node (ref "C40") (pin "1") (pinfunction "1_1") (pintype "passive"))
      (node (ref "C66") (pin "1") (pinfunction "1_1") (pintype "passive"))
      (node (ref "C85") (pin "1") (pinfunction "1_1") (pintype "passive"))
      (node (ref "C89") (pin "1") (pinfunction "1_1") (pintype "passive"))
      (node (ref "C90") (pin "1") (pinfunction "1_1") (pintype "passive"))
      (node (ref "C96") (pin "1") (pinfunction "1_1") (pintype "passive"))
      (node (ref "C97") (pin "1") (pinfunction "1_1") (pintype "passive"))
      (node (ref "C99") (pin "1") (pinfunction "1_1") (pintype "passive"))
      (node (ref "L2") (pin "1") (pinfunction "1_1") (pintype "passive"))
      (node (ref "R18") (pin "2") (pinfunction "2_2") (pintype "passive"))
      (node (ref "R68") (pin "2") (pinfunction "2_2") (pintype "passive"))
      (node (ref "U1") (pin "5") (pinfunction "VCC_5") (pintype "bidirectional"))
      (node (ref "U12") (pin "5") (pinfunction "V+_5") (pintype "bidirectional"))
      (node (ref "U13") (pin "5") (pinfunction "V+_5") (pintype "bidirectional"))
      (node (ref "U14") (pin "3") (pinfunction "VOUT_3") (pintype "bidirectional"))
      (node (ref "U15") (pin "5") (pinfunction "VCC_5") (pintype "bidirectional"))
      (node (ref "U16") (pin "5") (pinfunction "V+_5") (pintype "bidirectional"))
      (node (ref "U4") (pin "5") (pinfunction "VCC_5") (pintype "bidirectional"))
      (node (ref "U6") (pin "5") (pinfunction "VCC_5") (pintype "bidirectional"))
      (node (ref "U9") (pin "5") (pinfunction "VCC_5") (pintype "bidirectional"))
    )
    (net (code "35") (name "5V_USB1") (class "Default")
      (node (ref "C55") (pin "1") (pinfunction "1_1") (pintype "passive"))
      (node (ref "C56") (pin "1") (pinfunction "1_1") (pintype "passive"))
      (node (ref "C57") (pin "1") (pinfunction "1_1") (pintype "passive"))
      (node (ref "C60") (pin "1") (pinfunction "1_1") (pintype "passive"))
      (node (ref "C61") (pin "1") (pinfunction "1_1") (pintype "passive"))
      (node (ref "C62") (pin "1") (pinfunction "1_1") (pintype "passive"))
      (node (ref "D11") (pin "C") (pinfunction "C_C") (pintype "passive"))
      (node (ref "J2") (pin "9") (pinfunction "9_9") (pintype "bidirectional"))
      (node (ref "L5") (pin "2") (pinfunction "2_2") (pintype "passive"))
      (node (ref "R50") (pin "2") (pinfunction "2_2") (pintype "passive"))
      (node (ref "R52") (pin "2") (pinfunction "2_2") (pintype "passive"))
    )
    (net (code "36") (name "5V_USB2") (class "Default")
      (node (ref "C74") (pin "1") (pinfunction "1_1") (pintype "passive"))
      (node (ref "C75") (pin "1") (pinfunction "1_1") (pintype "passive"))
      (node (ref "C76") (pin "1") (pinfunction "1_1") (pintype "passive"))
      (node (ref "C78") (pin "1") (pinfunction "1_1") (pintype "passive"))
      (node (ref "C79") (pin "1") (pinfunction "1_1") (pintype "passive"))
      (node (ref "C80") (pin "1") (pinfunction "1_1") (pintype "passive"))
      (node (ref "D10") (pin "C") (pinfunction "C_C") (pintype "passive"))
      (node (ref "J2") (pin "10") (pinfunction "10_10") (pintype "bidirectional"))
      (node (ref "L6") (pin "2") (pinfunction "2_2") (pintype "passive"))
      (node (ref "R64") (pin "2") (pinfunction "2_2") (pintype "passive"))
      (node (ref "R65") (pin "2") (pinfunction "2_2") (pintype "passive"))
    )
    (net (code "37") (name "GND") (class "Default")
      (node (ref "C1") (pin "2") (pinfunction "2_2") (pintype "passive"))
      (node (ref "C10") (pin "2") (pinfunction "2_2") (pintype "passive"))
      (node (ref "C100") (pin "2") (pinfunction "2_2") (pintype "passive"))
      (node (ref "C101") (pin "2") (pinfunction "2_2") (pintype "passive"))
      (node (ref "C102") (pin "2") (pinfunction "2_2") (pintype "passive"))
      (node (ref "C103") (pin "2") (pinfunction "2_2") (pintype "passive"))
      (node (ref "C104") (pin "2") (pinfunction "2_2") (pintype "passive"))
      (node (ref "C105") (pin "2") (pinfunction "2_2") (pintype "passive"))
      (node (ref "C106") (pin "2") (pinfunction "2_2") (pintype "passive"))
      (node (ref "C107") (pin "2") (pinfunction "2_2") (pintype "passive"))
      (node (ref "C108") (pin "2") (pinfunction "2_2") (pintype "passive"))
      (node (ref "C109") (pin "2") (pinfunction "2_2") (pintype "passive"))
      (node (ref "C11") (pin "2") (pinfunction "2_2") (pintype "passive"))
      (node (ref "C110") (pin "-") (pinfunction "-_-") (pintype "passive"))
      (node (ref "C111") (pin "2") (pinfunction "2_2") (pintype "passive"))
      (node (ref "C112") (pin "2") (pinfunction "2_2") (pintype "passive"))
      (node (ref "C13") (pin "2") (pinfunction "2_2") (pintype "passive"))
      (node (ref "C14") (pin "2") (pinfunction "2_2") (pintype "passive"))
      (node (ref "C15") (pin "2") (pinfunction "2_2") (pintype "passive"))
      (node (ref "C19") (pin "2") (pinfunction "2_2") (pintype "passive"))
      (node (ref "C20") (pin "2") (pinfunction "2_2") (pintype "passive"))
      (node (ref "C21") (pin "2") (pinfunction "2_2") (pintype "passive"))
      (node (ref "C22") (pin "2") (pinfunction "2_2") (pintype "passive"))
      (node (ref "C23") (pin "2") (pinfunction "2_2") (pintype "passive"))
      (node (ref "C24") (pin "2") (pinfunction "2_2") (pintype "passive"))
      (node (ref "C26") (pin "2") (pinfunction "2_2") (pintype "passive"))
      (node (ref "C27") (pin "2") (pinfunction "2_2") (pintype "passive"))
      (node (ref "C28") (pin "2") (pinfunction "2_2") (pintype "passive"))
      (node (ref "C3") (pin "2") (pinfunction "2_2") (pintype "passive"))
      (node (ref "C30") (pin "2") (pinfunction "2_2") (pintype "passive"))
      (node (ref "C31") (pin "2") (pinfunction "2_2") (pintype "passive"))
      (node (ref "C32") (pin "2") (pinfunction "2_2") (pintype "passive"))
      (node (ref "C34") (pin "2") (pinfunction "2_2") (pintype "passive"))
      (node (ref "C35") (pin "2") (pinfunction "2_2") (pintype "passive"))
      (node (ref "C36") (pin "2") (pinfunction "2_2") (pintype "passive"))
      (node (ref "C4") (pin "2") (pinfunction "2_2") (pintype "passive"))
      (node (ref "C40") (pin "2") (pinfunction "2_2") (pintype "passive"))
      (node (ref "C42") (pin "2") (pinfunction "2_2") (pintype "passive"))
      (node (ref "C43") (pin "2") (pinfunction "2_2") (pintype "passive"))
      (node (ref "C44") (pin "2") (pinfunction "2_2") (pintype "passive"))
      (node (ref "C45") (pin "2") (pinfunction "2_2") (pintype "passive"))
      (node (ref "C46") (pin "2") (pinfunction "2_2") (pintype "passive"))
      (node (ref "C47") (pin "2") (pinfunction "2_2") (pintype "passive"))
      (node (ref "C48") (pin "2") (pinfunction "2_2") (pintype "passive"))
      (node (ref "C5") (pin "2") (pinfunction "2_2") (pintype "passive"))
      (node (ref "C50") (pin "2") (pinfunction "2_2") (pintype "passive"))
      (node (ref "C51") (pin "2") (pinfunction "2_2") (pintype "passive"))
      (node (ref "C52") (pin "2") (pinfunction "2_2") (pintype "passive"))
      (node (ref "C55") (pin "2") (pinfunction "2_2") (pintype "passive"))
      (node (ref "C56") (pin "2") (pinfunction "2_2") (pintype "passive"))
      (node (ref "C57") (pin "2") (pinfunction "2_2") (pintype "passive"))
      (node (ref "C6") (pin "2") (pinfunction "2_2") (pintype "passive"))
      (node (ref "C60") (pin "2") (pinfunction "2_2") (pintype "passive"))
      (node (ref "C61") (pin "2") (pinfunction "2_2") (pintype "passive"))
      (node (ref "C62") (pin "2") (pinfunction "2_2") (pintype "passive"))
      (node (ref "C66") (pin "2") (pinfunction "2_2") (pintype "passive"))
      (node (ref "C68") (pin "2") (pinfunction "2_2") (pintype "passive"))
      (node (ref "C69") (pin "2") (pinfunction "2_2") (pintype "passive"))
      (node (ref "C7") (pin "2") (pinfunction "2_2") (pintype "passive"))
      (node (ref "C70") (pin "2") (pinfunction "2_2") (pintype "passive"))
      (node (ref "C71") (pin "2") (pinfunction "2_2") (pintype "passive"))
      (node (ref "C72") (pin "2") (pinfunction "2_2") (pintype "passive"))
      (node (ref "C74") (pin "2") (pinfunction "2_2") (pintype "passive"))
      (node (ref "C75") (pin "2") (pinfunction "2_2") (pintype "passive"))
      (node (ref "C76") (pin "2") (pinfunction "2_2") (pintype "passive"))
      (node (ref "C78") (pin "2") (pinfunction "2_2") (pintype "passive"))
      (node (ref "C79") (pin "2") (pinfunction "2_2") (pintype "passive"))
      (node (ref "C80") (pin "2") (pinfunction "2_2") (pintype "passive"))
      (node (ref "C81") (pin "2") (pinfunction "2_2") (pintype "passive"))
      (node (ref "C82") (pin "2") (pinfunction "2_2") (pintype "passive"))
      (node (ref "C83") (pin "2") (pinfunction "2_2") (pintype "passive"))
      (node (ref "C84") (pin "2") (pinfunction "2_2") (pintype "passive"))
      (node (ref "C85") (pin "2") (pinfunction "2_2") (pintype "passive"))
      (node (ref "C87") (pin "2") (pinfunction "2_2") (pintype "passive"))
      (node (ref "C89") (pin "2") (pinfunction "2_2") (pintype "passive"))
      (node (ref "C9") (pin "2") (pinfunction "2_2") (pintype "passive"))
      (node (ref "C90") (pin "2") (pinfunction "2_2") (pintype "passive"))
      (node (ref "C91") (pin "2") (pinfunction "2_2") (pintype "passive"))
      (node (ref "C92") (pin "2") (pinfunction "2_2") (pintype "passive"))
      (node (ref "C93") (pin "2") (pinfunction "2_2") (pintype "passive"))
      (node (ref "C94") (pin "2") (pinfunction "2_2") (pintype "passive"))
      (node (ref "C95") (pin "2") (pinfunction "2_2") (pintype "passive"))
      (node (ref "C96") (pin "2") (pinfunction "2_2") (pintype "passive"))
      (node (ref "C97") (pin "2") (pinfunction "2_2") (pintype "passive"))
      (node (ref "C98") (pin "2") (pinfunction "2_2") (pintype "passive"))
      (node (ref "C99") (pin "2") (pinfunction "2_2") (pintype "passive"))
      (node (ref "D1") (pin "A") (pinfunction "A_A") (pintype "passive"))
      (node (ref "D10") (pin "A") (pinfunction "A_A") (pintype "passive"))
      (node (ref "D11") (pin "A") (pinfunction "A_A") (pintype "passive"))
      (node (ref "D12") (pin "A") (pinfunction "A_A") (pintype "passive"))
      (node (ref "D2") (pin "A") (pinfunction "A_A") (pintype "passive"))
      (node (ref "D4") (pin "A") (pinfunction "A_A") (pintype "passive"))
      (node (ref "D8") (pin "A") (pinfunction "A_A") (pintype "passive"))
      (node (ref "D9") (pin "A") (pinfunction "A_A") (pintype "passive"))
      (node (ref "J1") (pin "3") (pinfunction "GND_3") (pintype "bidirectional"))
      (node (ref "J2") (pin "1") (pinfunction "1_1") (pintype "bidirectional"))
      (node (ref "J2") (pin "2") (pinfunction "2_2") (pintype "bidirectional"))
      (node (ref "J2") (pin "3") (pinfunction "3_3") (pintype "bidirectional"))
      (node (ref "J2") (pin "4") (pinfunction "4_4") (pintype "bidirectional"))
      (node (ref "P1") (pin "1") (pinfunction "P$1_1") (pintype "bidirectional"))
      (node (ref "P10") (pin "1") (pinfunction "P$1_1") (pintype "bidirectional"))
      (node (ref "P11") (pin "1") (pinfunction "P$1_1") (pintype "bidirectional"))
      (node (ref "P4") (pin "1") (pinfunction "P$1_1") (pintype "bidirectional"))
      (node (ref "P5") (pin "1") (pinfunction "P$1_1") (pintype "bidirectional"))
      (node (ref "P7") (pin "1") (pinfunction "P$1_1") (pintype "bidirectional"))
      (node (ref "Q10") (pin "2") (pinfunction "S_2") (pintype "bidirectional"))
      (node (ref "Q12") (pin "2") (pinfunction "S_2") (pintype "bidirectional"))
      (node (ref "Q13") (pin "5") (pinfunction "S2_5") (pintype "bidirectional"))
      (node (ref "Q13") (pin "6") (pinfunction "S2_6") (pintype "bidirectional"))
      (node (ref "Q13") (pin "7") (pinfunction "S2_7") (pintype "bidirectional"))
      (node (ref "Q15") (pin "2") (pinfunction "S_2") (pintype "bidirectional"))
      (node (ref "Q16") (pin "5") (pinfunction "S2_5") (pintype "bidirectional"))
      (node (ref "Q16") (pin "6") (pinfunction "S2_6") (pintype "bidirectional"))
      (node (ref "Q16") (pin "7") (pinfunction "S2_7") (pintype "bidirectional"))
      (node (ref "Q17") (pin "5") (pinfunction "S2_5") (pintype "bidirectional"))
      (node (ref "Q17") (pin "6") (pinfunction "S2_6") (pintype "bidirectional"))
      (node (ref "Q17") (pin "7") (pinfunction "S2_7") (pintype "bidirectional"))
      (node (ref "Q2") (pin "2") (pinfunction "S_2") (pintype "bidirectional"))
      (node (ref "Q3") (pin "5") (pinfunction "S2_5") (pintype "bidirectional"))
      (node (ref "Q3") (pin "6") (pinfunction "S2_6") (pintype "bidirectional"))
      (node (ref "Q3") (pin "7") (pinfunction "S2_7") (pintype "bidirectional"))
      (node (ref "Q5") (pin "2") (pinfunction "S_2") (pintype "bidirectional"))
      (node (ref "Q7") (pin "5") (pinfunction "S2_5") (pintype "bidirectional"))
      (node (ref "Q7") (pin "6") (pinfunction "S2_6") (pintype "bidirectional"))
      (node (ref "Q7") (pin "7") (pinfunction "S2_7") (pintype "bidirectional"))
      (node (ref "Q8") (pin "2") (pinfunction "S_2") (pintype "bidirectional"))
      (node (ref "R10") (pin "1") (pinfunction "1_1") (pintype "passive"))
      (node (ref "R13") (pin "1") (pinfunction "1_1") (pintype "passive"))
      (node (ref "R15") (pin "1") (pinfunction "1_1") (pintype "passive"))
      (node (ref "R17") (pin "1") (pinfunction "1_1") (pintype "passive"))
      (node (ref "R2") (pin "1") (pinfunction "1_1") (pintype "passive"))
      (node (ref "R29") (pin "1") (pinfunction "1_1") (pintype "passive"))
      (node (ref "R30") (pin "1") (pinfunction "1_1") (pintype "passive"))
      (node (ref "R34") (pin "1") (pinfunction "1_1") (pintype "passive"))
      (node (ref "R37") (pin "1") (pinfunction "1_1") (pintype "passive"))
      (node (ref "R39") (pin "1") (pinfunction "1_1") (pintype "passive"))
      (node (ref "R41") (pin "1") (pinfunction "1_1") (pintype "passive"))
      (node (ref "R45") (pin "1") (pinfunction "1_1") (pintype "passive"))
      (node (ref "R49") (pin "1") (pinfunction "1_1") (pintype "passive"))
      (node (ref "R53") (pin "1") (pinfunction "1_1") (pintype "passive"))
      (node (ref "R57") (pin "1") (pinfunction "1_1") (pintype "passive"))
      (node (ref "R59") (pin "1") (pinfunction "1_1") (pintype "passive"))
      (node (ref "R6") (pin "1") (pinfunction "1_1") (pintype "passive"))
      (node (ref "R63") (pin "1") (pinfunction "1_1") (pintype "passive"))
      (node (ref "R66") (pin "1") (pinfunction "1_1") (pintype "passive"))
      (node (ref "R67") (pin "1") (pinfunction "1_1") (pintype "passive"))
      (node (ref "R70") (pin "1") (pinfunction "1_1") (pintype "passive"))
      (node (ref "R71") (pin "1") (pinfunction "1_1") (pintype "passive"))
      (node (ref "R73") (pin "1") (pinfunction "1_1") (pintype "passive"))
      (node (ref "R75") (pin "1") (pinfunction "1_1") (pintype "passive"))
      (node (ref "R77") (pin "1") (pinfunction "1_1") (pintype "passive"))
      (node (ref "U1") (pin "2") (pinfunction "GND_2") (pintype "bidirectional"))
      (node (ref "U10") (pin "EP") (pinfunction "GND_EP") (pintype "bidirectional"))
      (node (ref "U11") (pin "4") (pinfunction "GND/ADJ_4") (pintype "bidirectional"))
      (node (ref "U12") (pin "2") (pinfunction "V-_2") (pintype "bidirectional"))
      (node (ref "U13") (pin "2") (pinfunction "V-_2") (pintype "bidirectional"))
      (node (ref "U14") (pin "4") (pinfunction "GND/ADJ_4") (pintype "bidirectional"))
      (node (ref "U15") (pin "2") (pinfunction "GND_2") (pintype "bidirectional"))
      (node (ref "U16") (pin "2") (pinfunction "V-_2") (pintype "bidirectional"))
      (node (ref "U2") (pin "EP") (pinfunction "GND_EP") (pintype "bidirectional"))
      (node (ref "U3") (pin "19") (pinfunction "VSS_19") (pintype "bidirectional"))
      (node (ref "U3") (pin "8") (pinfunction "VSS_8") (pintype "bidirectional"))
      (node (ref "U4") (pin "2") (pinfunction "GND_2") (pintype "bidirectional"))
      (node (ref "U5") (pin "EP") (pinfunction "GND_EP") (pintype "bidirectional"))
      (node (ref "U6") (pin "2") (pinfunction "GND_2") (pintype "bidirectional"))
      (node (ref "U7") (pin "EP") (pinfunction "GND_EP") (pintype "bidirectional"))
      (node (ref "U8") (pin "EP") (pinfunction "GND_EP") (pintype "bidirectional"))
      (node (ref "U9") (pin "2") (pinfunction "GND_2") (pintype "bidirectional"))
    )
    (net (code "38") (name "Net-(C12-Pad1)") (class "Default")
      (node (ref "C12") (pin "1") (pinfunction "1_1") (pintype "passive"))
      (node (ref "R8") (pin "1") (pinfunction "1_1") (pintype "passive"))
    )
    (net (code "39") (name "Net-(C16-Pad2)") (class "Default")
      (node (ref "C16") (pin "2") (pinfunction "2_2") (pintype "passive"))
      (node (ref "R11") (pin "2") (pinfunction "2_2") (pintype "passive"))
    )
    (net (code "40") (name "Net-(C33-Pad1)") (class "Default")
      (node (ref "C33") (pin "1") (pinfunction "1_1") (pintype "passive"))
      (node (ref "R27") (pin "1") (pinfunction "1_1") (pintype "passive"))
    )
    (net (code "41") (name "Net-(C37-Pad2)") (class "Default")
      (node (ref "C37") (pin "2") (pinfunction "2_2") (pintype "passive"))
      (node (ref "R32") (pin "2") (pinfunction "2_2") (pintype "passive"))
    )
    (net (code "42") (name "Net-(C53-Pad1)") (class "Default")
      (node (ref "C53") (pin "1") (pinfunction "1_1") (pintype "passive"))
      (node (ref "R51") (pin "1") (pinfunction "1_1") (pintype "passive"))
    )
    (net (code "43") (name "Net-(C58-Pad2)") (class "Default")
      (node (ref "C58") (pin "2") (pinfunction "2_2") (pintype "passive"))
      (node (ref "R55") (pin "2") (pinfunction "2_2") (pintype "passive"))
    )
    (net (code "44") (name "Net-(C59-Pad1)") (class "Default")
      (node (ref "C59") (pin "1") (pinfunction "1_1") (pintype "passive"))
      (node (ref "R50") (pin "1") (pinfunction "1_1") (pintype "passive"))
    )
    (net (code "45") (name "Net-(C64-Pad2)") (class "Default")
      (node (ref "C64") (pin "2") (pinfunction "2_2") (pintype "passive"))
      (node (ref "R56") (pin "2") (pinfunction "2_2") (pintype "passive"))
    )
    (net (code "46") (name "Net-(C77-Pad1)") (class "Default")
      (node (ref "C77") (pin "1") (pinfunction "1_1") (pintype "passive"))
      (node (ref "R64") (pin "1") (pinfunction "1_1") (pintype "passive"))
    )
    (net (code "47") (name "Net-(C86-Pad2)") (class "Default")
      (node (ref "C86") (pin "2") (pinfunction "2_2") (pintype "passive"))
      (node (ref "R69") (pin "2") (pinfunction "2_2") (pintype "passive"))
    )
    (net (code "48") (name "Net-(C106-Pad1)") (class "Default")
      (node (ref "C106") (pin "1") (pinfunction "1_1") (pintype "passive"))
      (node (ref "C83") (pin "1") (pinfunction "1_1") (pintype "passive"))
      (node (ref "C84") (pin "1") (pinfunction "1_1") (pintype "passive"))
      (node (ref "C91") (pin "1") (pinfunction "1_1") (pintype "passive"))
      (node (ref "D16") (pin "A@1") (pinfunction "A_A@1") (pintype "passive"))
      (node (ref "D16") (pin "A@2") (pinfunction "A_A@2") (pintype "passive"))
      (node (ref "L4") (pin "2") (pinfunction "2_2") (pintype "passive"))
      (node (ref "R48") (pin "2") (pinfunction "2_2") (pintype "passive"))
      (node (ref "R51") (pin "2") (pinfunction "2_2") (pintype "passive"))
    )
    (net (code "49") (name "Net-(D3-A-PadA@1)") (class "Default")
      (node (ref "D3") (pin "A@1") (pinfunction "A_A@1") (pintype "passive"))
      (node (ref "D3") (pin "A@2") (pinfunction "A_A@2") (pintype "passive"))
      (node (ref "Q4") (pin "5") (pinfunction "D_5") (pintype "bidirectional"))
      (node (ref "Q4") (pin "6") (pinfunction "D_6") (pintype "bidirectional"))
      (node (ref "Q4") (pin "7") (pinfunction "D_7") (pintype "bidirectional"))
      (node (ref "Q4") (pin "8") (pinfunction "D_8") (pintype "bidirectional"))
      (node (ref "Q4") (pin "EP") (pinfunction "D_EP") (pintype "bidirectional"))
      (node (ref "R15") (pin "2") (pinfunction "2_2") (pintype "passive"))
    )
    (net (code "50") (name "Net-(D5-A-PadA@1)") (class "Default")
      (node (ref "D5") (pin "A@1") (pinfunction "A_A@1") (pintype "passive"))
      (node (ref "D5") (pin "A@2") (pinfunction "A_A@2") (pintype "passive"))
      (node (ref "Q6") (pin "5") (pinfunction "D_5") (pintype "bidirectional"))
      (node (ref "Q6") (pin "6") (pinfunction "D_6") (pintype "bidirectional"))
      (node (ref "Q6") (pin "7") (pinfunction "D_7") (pintype "bidirectional"))
      (node (ref "Q6") (pin "8") (pinfunction "D_8") (pintype "bidirectional"))
      (node (ref "Q6") (pin "EP") (pinfunction "D_EP") (pintype "bidirectional"))
      (node (ref "R10") (pin "2") (pinfunction "2_2") (pintype "passive"))
    )
    (net (code "51") (name "Net-(D6-A-PadA@1)") (class "Default")
      (node (ref "D6") (pin "A@1") (pinfunction "A_A@1") (pintype "passive"))
      (node (ref "D6") (pin "A@2") (pinfunction "A_A@2") (pintype "passive"))
      (node (ref "Q1") (pin "5") (pinfunction "D_5") (pintype "bidirectional"))
      (node (ref "Q1") (pin "6") (pinfunction "D_6") (pintype "bidirectional"))
      (node (ref "Q1") (pin "7") (pinfunction "D_7") (pintype "bidirectional"))
      (node (ref "Q1") (pin "8") (pinfunction "D_8") (pintype "bidirectional"))
      (node (ref "Q1") (pin "EP") (pinfunction "D_EP") (pintype "bidirectional"))
      (node (ref "R2") (pin "2") (pinfunction "2_2") (pintype "passive"))
    )
    (net (code "52") (name "Net-(D7-A-PadA@1)") (class "Default")
      (node (ref "D7") (pin "A@1") (pinfunction "A_A@1") (pintype "passive"))
      (node (ref "D7") (pin "A@2") (pinfunction "A_A@2") (pintype "passive"))
      (node (ref "Q9") (pin "5") (pinfunction "D_5") (pintype "bidirectional"))
      (node (ref "Q9") (pin "6") (pinfunction "D_6") (pintype "bidirectional"))
      (node (ref "Q9") (pin "7") (pinfunction "D_7") (pintype "bidirectional"))
      (node (ref "Q9") (pin "8") (pinfunction "D_8") (pintype "bidirectional"))
      (node (ref "Q9") (pin "EP") (pinfunction "D_EP") (pintype "bidirectional"))
      (node (ref "R39") (pin "2") (pinfunction "2_2") (pintype "passive"))
    )
    (net (code "53") (name "Net-(D13-A-PadA@1)") (class "Default")
      (node (ref "D13") (pin "A@1") (pinfunction "A_A@1") (pintype "passive"))
      (node (ref "D13") (pin "A@2") (pinfunction "A_A@2") (pintype "passive"))
      (node (ref "Q11") (pin "5") (pinfunction "D_5") (pintype "bidirectional"))
      (node (ref "Q11") (pin "6") (pinfunction "D_6") (pintype "bidirectional"))
      (node (ref "Q11") (pin "7") (pinfunction "D_7") (pintype "bidirectional"))
      (node (ref "Q11") (pin "8") (pinfunction "D_8") (pintype "bidirectional"))
      (node (ref "Q11") (pin "EP") (pinfunction "D_EP") (pintype "bidirectional"))
      (node (ref "R30") (pin "2") (pinfunction "2_2") (pintype "passive"))
    )
    (net (code "54") (name "Net-(D14-A-PadA@1)") (class "Default")
      (node (ref "D14") (pin "A@1") (pinfunction "A_A@1") (pintype "passive"))
      (node (ref "D14") (pin "A@2") (pinfunction "A_A@2") (pintype "passive"))
      (node (ref "Q14") (pin "5") (pinfunction "D_5") (pintype "bidirectional"))
      (node (ref "Q14") (pin "6") (pinfunction "D_6") (pintype "bidirectional"))
      (node (ref "Q14") (pin "7") (pinfunction "D_7") (pintype "bidirectional"))
      (node (ref "Q14") (pin "8") (pinfunction "D_8") (pintype "bidirectional"))
      (node (ref "Q14") (pin "EP") (pinfunction "D_EP") (pintype "bidirectional"))
      (node (ref "R59") (pin "2") (pinfunction "2_2") (pintype "passive"))
    )
    (net (code "55") (name "Net-(J1-VCC)") (class "Default")
      (node (ref "J1") (pin "2") (pinfunction "VCC_2") (pintype "bidirectional"))
      (node (ref "R68") (pin "1") (pinfunction "1_1") (pintype "passive"))
    )
    (net (code "56") (name "Net-(J2-Pad5)") (class "Default")
      (node (ref "J2") (pin "5") (pinfunction "5_5") (pintype "bidirectional"))
      (node (ref "R81") (pin "1") (pinfunction "1_1") (pintype "passive"))
    )
    (net (code "57") (name "Net-(J2-Pad6)") (class "Default")
      (node (ref "J2") (pin "6") (pinfunction "6_6") (pintype "bidirectional"))
      (node (ref "R78") (pin "1") (pinfunction "1_1") (pintype "passive"))
    )
    (net (code "58") (name "Net-(J2-Pad7)") (class "Default")
      (node (ref "J2") (pin "7") (pinfunction "7_7") (pintype "bidirectional"))
      (node (ref "R81") (pin "2") (pinfunction "2_2") (pintype "passive"))
    )
    (net (code "59") (name "Net-(J2-Pad8)") (class "Default")
      (node (ref "J2") (pin "8") (pinfunction "8_8") (pintype "bidirectional"))
      (node (ref "R78") (pin "2") (pinfunction "2_2") (pintype "passive"))
    )
    (net (code "60") (name "Net-(L1-1)") (class "Default")
      (node (ref "C8") (pin "2") (pinfunction "2_2") (pintype "passive"))
      (node (ref "L1") (pin "P$1") (pinfunction "1_P$1") (pintype "passive"))
      (node (ref "Q3") (pin "EP2") (pinfunction "S1D2_EP2") (pintype "bidirectional"))
      (node (ref "U2") (pin "9") (pinfunction "PHASE_9") (pintype "bidirectional"))
    )
    (net (code "61") (name "Net-(L3-1)") (class "Default")
      (node (ref "C29") (pin "2") (pinfunction "2_2") (pintype "passive"))
      (node (ref "L3") (pin "P$1") (pinfunction "1_P$1") (pintype "passive"))
      (node (ref "Q7") (pin "EP2") (pinfunction "S1D2_EP2") (pintype "bidirectional"))
      (node (ref "U5") (pin "9") (pinfunction "PHASE_9") (pintype "bidirectional"))
    )
    (net (code "62") (name "Net-(P3-P$1)") (class "Default")
      (node (ref "C110") (pin "+") (pinfunction "+_+") (pintype "passive"))
      (node (ref "D2") (pin "C") (pinfunction "C_C") (pintype "passive"))
      (node (ref "F1") (pin "1") (pinfunction "1_1") (pintype "bidirectional"))
      (node (ref "P3") (pin "1") (pinfunction "P$1_1") (pintype "bidirectional"))
    )
    (net (code "63") (name "Net-(Q1-G)") (class "Default")
      (node (ref "C2") (pin "2") (pinfunction "2_2") (pintype "passive"))
      (node (ref "Q1") (pin "4") (pinfunction "G_4") (pintype "bidirectional"))
      (node (ref "R1") (pin "1") (pinfunction "1_1") (pintype "passive"))
      (node (ref "R3") (pin "2") (pinfunction "2_2") (pintype "passive"))
    )
    (net (code "64") (name "Net-(Q2-D)") (class "Default")
      (node (ref "Q2") (pin "3") (pinfunction "D_3") (pintype "bidirectional"))
      (node (ref "R3") (pin "1") (pinfunction "1_1") (pintype "passive"))
    )
    (net (code "65") (name "Net-(Q3-G1)") (class "Default")
      (node (ref "Q3") (pin "1") (pinfunction "G1_1") (pintype "bidirectional"))
      (node (ref "U2") (pin "10") (pinfunction "HDRV_10") (pintype "bidirectional"))
    )
    (net (code "66") (name "Net-(Q3-G2)") (class "Default")
      (node (ref "Q3") (pin "8") (pinfunction "G2_8") (pintype "bidirectional"))
      (node (ref "U2") (pin "7") (pinfunction "LDRV_7") (pintype "bidirectional"))
    )
    (net (code "67") (name "Net-(Q4-G)") (class "Default")
      (node (ref "C18") (pin "2") (pinfunction "2_2") (pintype "passive"))
      (node (ref "Q4") (pin "4") (pinfunction "G_4") (pintype "bidirectional"))
      (node (ref "R14") (pin "1") (pinfunction "1_1") (pintype "passive"))
      (node (ref "R16") (pin "2") (pinfunction "2_2") (pintype "passive"))
    )
    (net (code "68") (name "Net-(Q5-D)") (class "Default")
      (node (ref "Q5") (pin "3") (pinfunction "D_3") (pintype "bidirectional"))
      (node (ref "R16") (pin "1") (pinfunction "1_1") (pintype "passive"))
    )
    (net (code "69") (name "Net-(Q6-G)") (class "Default")
      (node (ref "C25") (pin "2") (pinfunction "2_2") (pintype "passive"))
      (node (ref "Q6") (pin "4") (pinfunction "G_4") (pintype "bidirectional"))
      (node (ref "R20") (pin "1") (pinfunction "1_1") (pintype "passive"))
      (node (ref "R24") (pin "2") (pinfunction "2_2") (pintype "passive"))
    )
    (net (code "70") (name "Net-(Q7-G1)") (class "Default")
      (node (ref "Q7") (pin "1") (pinfunction "G1_1") (pintype "bidirectional"))
      (node (ref "U5") (pin "10") (pinfunction "HDRV_10") (pintype "bidirectional"))
    )
    (net (code "71") (name "Net-(Q7-G2)") (class "Default")
      (node (ref "Q7") (pin "8") (pinfunction "G2_8") (pintype "bidirectional"))
      (node (ref "U5") (pin "7") (pinfunction "LDRV_7") (pintype "bidirectional"))
    )
    (net (code "72") (name "Net-(Q8-D)") (class "Default")
      (node (ref "Q8") (pin "3") (pinfunction "D_3") (pintype "bidirectional"))
      (node (ref "R24") (pin "1") (pinfunction "1_1") (pintype "passive"))
    )
    (net (code "73") (name "Net-(Q9-G)") (class "Default")
      (node (ref "C39") (pin "2") (pinfunction "2_2") (pintype "passive"))
      (node (ref "Q9") (pin "4") (pinfunction "G_4") (pintype "bidirectional"))
      (node (ref "R38") (pin "1") (pinfunction "1_1") (pintype "passive"))
      (node (ref "R40") (pin "2") (pinfunction "2_2") (pintype "passive"))
    )
    (net (code "74") (name "Net-(Q10-D)") (class "Default")
      (node (ref "Q10") (pin "3") (pinfunction "D_3") (pintype "bidirectional"))
      (node (ref "R40") (pin "1") (pinfunction "1_1") (pintype "passive"))
    )
    (net (code "75") (name "Net-(Q11-G)") (class "Default")
      (node (ref "C41") (pin "2") (pinfunction "2_2") (pintype "passive"))
      (node (ref "Q11") (pin "4") (pinfunction "G_4") (pintype "bidirectional"))
      (node (ref "R42") (pin "1") (pinfunction "1_1") (pintype "passive"))
      (node (ref "R43") (pin "2") (pinfunction "2_2") (pintype "passive"))
    )
    (net (code "76") (name "Net-(Q12-D)") (class "Default")
      (node (ref "Q12") (pin "3") (pinfunction "D_3") (pintype "bidirectional"))
      (node (ref "R43") (pin "1") (pinfunction "1_1") (pintype "passive"))
    )
    (net (code "77") (name "Net-(Q13-G1)") (class "Default")
      (node (ref "Q13") (pin "1") (pinfunction "G1_1") (pintype "bidirectional"))
      (node (ref "U8") (pin "10") (pinfunction "HDRV_10") (pintype "bidirectional"))
    )
    (net (code "78") (name "Net-(Q13-G2)") (class "Default")
      (node (ref "Q13") (pin "8") (pinfunction "G2_8") (pintype "bidirectional"))
      (node (ref "U8") (pin "7") (pinfunction "LDRV_7") (pintype "bidirectional"))
    )
    (net (code "79") (name "Net-(Q13-S1D2)") (class "Default")
      (node (ref "C54") (pin "2") (pinfunction "2_2") (pintype "passive"))
      (node (ref "L5") (pin "1") (pinfunction "1_1") (pintype "passive"))
      (node (ref "Q13") (pin "EP2") (pinfunction "S1D2_EP2") (pintype "bidirectional"))
      (node (ref "U8") (pin "9") (pinfunction "PHASE_9") (pintype "bidirectional"))
    )
    (net (code "80") (name "Net-(Q14-G)") (class "Default")
      (node (ref "C67") (pin "2") (pinfunction "2_2") (pintype "passive"))
      (node (ref "Q14") (pin "4") (pinfunction "G_4") (pintype "bidirectional"))
      (node (ref "R58") (pin "1") (pinfunction "1_1") (pintype "passive"))
      (node (ref "R60") (pin "2") (pinfunction "2_2") (pintype "passive"))
    )
    (net (code "81") (name "Net-(Q15-D)") (class "Default")
      (node (ref "Q15") (pin "3") (pinfunction "D_3") (pintype "bidirectional"))
      (node (ref "R60") (pin "1") (pinfunction "1_1") (pintype "passive"))
    )
    (net (code "82") (name "Net-(Q16-G1)") (class "Default")
      (node (ref "Q16") (pin "1") (pinfunction "G1_1") (pintype "bidirectional"))
      (node (ref "U10") (pin "10") (pinfunction "HDRV_10") (pintype "bidirectional"))
    )
    (net (code "83") (name "Net-(Q16-G2)") (class "Default")
      (node (ref "Q16") (pin "8") (pinfunction "G2_8") (pintype "bidirectional"))
      (node (ref "U10") (pin "7") (pinfunction "LDRV_7") (pintype "bidirectional"))
    )
    (net (code "84") (name "Net-(Q16-S1D2)") (class "Default")
      (node (ref "C73") (pin "2") (pinfunction "2_2") (pintype "passive"))
      (node (ref "L6") (pin "1") (pinfunction "1_1") (pintype "passive"))
      (node (ref "Q16") (pin "EP2") (pinfunction "S1D2_EP2") (pintype "bidirectional"))
      (node (ref "U10") (pin "9") (pinfunction "PHASE_9") (pintype "bidirectional"))
    )
    (net (code "85") (name "Net-(Q17-G1)") (class "Default")
      (node (ref "Q17") (pin "1") (pinfunction "G1_1") (pintype "bidirectional"))
      (node (ref "U7") (pin "10") (pinfunction "HDRV_10") (pintype "bidirectional"))
    )
    (net (code "86") (name "Net-(Q17-G2)") (class "Default")
      (node (ref "Q17") (pin "8") (pinfunction "G2_8") (pintype "bidirectional"))
      (node (ref "U7") (pin "7") (pinfunction "LDRV_7") (pintype "bidirectional"))
    )
    (net (code "87") (name "Net-(Q17-S1D2)") (class "Default")
      (node (ref "C49") (pin "2") (pinfunction "2_2") (pintype "passive"))
      (node (ref "L4") (pin "1") (pinfunction "1_1") (pintype "passive"))
      (node (ref "Q17") (pin "EP2") (pinfunction "S1D2_EP2") (pintype "bidirectional"))
      (node (ref "U7") (pin "9") (pinfunction "PHASE_9") (pintype "bidirectional"))
    )
    (net (code "88") (name "Net-(R12-Pad1)") (class "Default")
      (node (ref "R12") (pin "1") (pinfunction "1_1") (pintype "passive"))
      (node (ref "R13") (pin "2") (pinfunction "2_2") (pintype "passive"))
    )
    (net (code "89") (name "Net-(R33-Pad1)") (class "Default")
      (node (ref "R33") (pin "1") (pinfunction "1_1") (pintype "passive"))
      (node (ref "R34") (pin "2") (pinfunction "2_2") (pintype "passive"))
    )
    (net (code "90") (name "Net-(U1-VM)") (class "Default")
      (node (ref "F2") (pin "2") (pinfunction "2_2") (pintype "bidirectional"))
      (node (ref "R4") (pin "1") (pinfunction "1_1") (pintype "passive"))
      (node (ref "U1") (pin "4") (pinfunction "VM_4") (pintype "bidirectional"))
    )
    (net (code "91") (name "Net-(U1-VP)") (class "Default")
      (node (ref "D6") (pin "C") (pinfunction "C_C") (pintype "passive"))
      (node (ref "R4") (pin "2") (pinfunction "2_2") (pintype "passive"))
      (node (ref "U1") (pin "3") (pinfunction "VP_3") (pintype "bidirectional"))
    )
    (net (code "92") (name "Net-(U2-BOOT)") (class "Default")
      (node (ref "C8") (pin "1") (pinfunction "1_1") (pintype "passive"))
      (node (ref "U2") (pin "8") (pinfunction "BOOT_8") (pintype "bidirectional"))
    )
    (net (code "93") (name "Net-(U2-COMP)") (class "Default")
      (node (ref "C16") (pin "1") (pinfunction "1_1") (pintype "passive"))
      (node (ref "C17") (pin "1") (pinfunction "1_1") (pintype "passive"))
      (node (ref "U2") (pin "3") (pinfunction "COMP_3") (pintype "bidirectional"))
    )
    (net (code "94") (name "Net-(U2-FB)") (class "Default")
      (node (ref "C12") (pin "2") (pinfunction "2_2") (pintype "passive"))
      (node (ref "C17") (pin "2") (pinfunction "2_2") (pintype "passive"))
      (node (ref "R11") (pin "1") (pinfunction "1_1") (pintype "passive"))
      (node (ref "R12") (pin "2") (pinfunction "2_2") (pintype "passive"))
      (node (ref "R31") (pin "1") (pinfunction "1_1") (pintype "passive"))
      (node (ref "R9") (pin "1") (pinfunction "1_1") (pintype "passive"))
      (node (ref "U2") (pin "2") (pinfunction "FB_2") (pintype "bidirectional"))
    )
    (net (code "95") (name "Net-(U2-VCC)") (class "Default")
      (node (ref "C92") (pin "1") (pinfunction "1_1") (pintype "passive"))
      (node (ref "U2") (pin "6") (pinfunction "VCC_6") (pintype "bidirectional"))
    )
    (net (code "96") (name "Net-(U2-VIN)") (class "Default")
      (node (ref "C7") (pin "1") (pinfunction "1_1") (pintype "passive"))
      (node (ref "R5") (pin "2") (pinfunction "2_2") (pintype "passive"))
      (node (ref "R7") (pin "2") (pinfunction "2_2") (pintype "passive"))
      (node (ref "U2") (pin "4") (pinfunction "VIN_4") (pintype "bidirectional"))
    )
    (net (code "97") (name "Net-(U2-~{SHDN})") (class "Default")
      (node (ref "C111") (pin "1") (pinfunction "1_1") (pintype "passive"))
      (node (ref "R7") (pin "1") (pinfunction "1_1") (pintype "passive"))
      (node (ref "U2") (pin "1") (pinfunction "~{SHDN}_1") (pintype "bidirectional"))
    )
    (net (code "98") (name "Net-(U3-RB6{slash}DAC[5,7]REF1+{slash}C4IN1+{slash}ICSPCLK)") (class "Default")
      (node (ref "R22") (pin "1") (pinfunction "1_1") (pintype "passive"))
      (node (ref "U3") (pin "27") (pinfunction "RB6/DAC[5,7]REF1+/C4IN1+/ICSPCLK_27") (pintype "bidirectional"))
    )
    (net (code "99") (name "Net-(U3-RB7{slash}C5IN1+{slash}DAC[1-7]OUT2{slash}T6IN{slash}ICSPDAT)") (class "Default")
      (node (ref "R25") (pin "1") (pinfunction "1_1") (pintype "passive"))
      (node (ref "U3") (pin "28") (pinfunction "RB7/C5IN1+/DAC[1-7]OUT2/T6IN/ICSPDAT_28") (pintype "bidirectional"))
    )
    (net (code "100") (name "Net-(U3-RE3{slash}~{MCLR})") (class "Default")
      (node (ref "R19") (pin "2") (pinfunction "2_2") (pintype "passive"))
      (node (ref "U3") (pin "1") (pinfunction "RE3/~{MCLR}_1") (pintype "bidirectional"))
    )
    (net (code "101") (name "Net-(U3-VDD)") (class "Default")
      (node (ref "C19") (pin "1") (pinfunction "1_1") (pintype "passive"))
      (node (ref "C20") (pin "1") (pinfunction "1_1") (pintype "passive"))
      (node (ref "L2") (pin "2") (pinfunction "2_2") (pintype "passive"))
      (node (ref "U3") (pin "20") (pinfunction "VDD_20") (pintype "bidirectional"))
    )
    (net (code "102") (name "Net-(U4-VM)") (class "Default")
      (node (ref "F3") (pin "2") (pinfunction "2_2") (pintype "bidirectional"))
      (node (ref "R26") (pin "1") (pinfunction "1_1") (pintype "passive"))
      (node (ref "U4") (pin "4") (pinfunction "VM_4") (pintype "bidirectional"))
    )
    (net (code "103") (name "Net-(U4-VP)") (class "Default")
      (node (ref "D3") (pin "C") (pinfunction "C_C") (pintype "passive"))
      (node (ref "D5") (pin "C") (pinfunction "C_C") (pintype "passive"))
      (node (ref "R26") (pin "2") (pinfunction "2_2") (pintype "passive"))
      (node (ref "U4") (pin "3") (pinfunction "VP_3") (pintype "bidirectional"))
    )
    (net (code "104") (name "Net-(U5-BOOT)") (class "Default")
      (node (ref "C29") (pin "1") (pinfunction "1_1") (pintype "passive"))
      (node (ref "U5") (pin "8") (pinfunction "BOOT_8") (pintype "bidirectional"))
    )
    (net (code "105") (name "Net-(U5-COMP)") (class "Default")
      (node (ref "C37") (pin "1") (pinfunction "1_1") (pintype "passive"))
      (node (ref "C38") (pin "1") (pinfunction "1_1") (pintype "passive"))
      (node (ref "U5") (pin "3") (pinfunction "COMP_3") (pintype "bidirectional"))
    )
    (net (code "106") (name "Net-(U5-FB)") (class "Default")
      (node (ref "C33") (pin "2") (pinfunction "2_2") (pintype "passive"))
      (node (ref "C38") (pin "2") (pinfunction "2_2") (pintype "passive"))
      (node (ref "R28") (pin "1") (pinfunction "1_1") (pintype "passive"))
      (node (ref "R32") (pin "1") (pinfunction "1_1") (pintype "passive"))
      (node (ref "R33") (pin "2") (pinfunction "2_2") (pintype "passive"))
      (node (ref "R35") (pin "1") (pinfunction "1_1") (pintype "passive"))
      (node (ref "U5") (pin "2") (pinfunction "FB_2") (pintype "bidirectional"))
    )
    (net (code "107") (name "Net-(U5-VCC)") (class "Default")
      (node (ref "C93") (pin "1") (pinfunction "1_1") (pintype "passive"))
      (node (ref "U5") (pin "6") (pinfunction "VCC_6") (pintype "bidirectional"))
    )
    (net (code "108") (name "Net-(U5-VIN)") (class "Default")
      (node (ref "C28") (pin "1") (pinfunction "1_1") (pintype "passive"))
      (node (ref "R21") (pin "2") (pinfunction "2_2") (pintype "passive"))
      (node (ref "R23") (pin "2") (pinfunction "2_2") (pintype "passive"))
      (node (ref "U5") (pin "4") (pinfunction "VIN_4") (pintype "bidirectional"))
    )
    (net (code "109") (name "Net-(U5-~{SHDN})") (class "Default")
      (node (ref "C112") (pin "1") (pinfunction "1_1") (pintype "passive"))
      (node (ref "R23") (pin "1") (pinfunction "1_1") (pintype "passive"))
      (node (ref "U5") (pin "1") (pinfunction "~{SHDN}_1") (pintype "bidirectional"))
    )
    (net (code "110") (name "Net-(U6-VM)") (class "Default")
      (node (ref "F4") (pin "2") (pinfunction "2_2") (pintype "bidirectional"))
      (node (ref "R44") (pin "1") (pinfunction "1_1") (pintype "passive"))
      (node (ref "U6") (pin "4") (pinfunction "VM_4") (pintype "bidirectional"))
    )
    (net (code "111") (name "Net-(U6-VP)") (class "Default")
      (node (ref "D13") (pin "C") (pinfunction "C_C") (pintype "passive"))
      (node (ref "D7") (pin "C") (pinfunction "C_C") (pintype "passive"))
      (node (ref "R44") (pin "2") (pinfunction "2_2") (pintype "passive"))
      (node (ref "U6") (pin "3") (pinfunction "VP_3") (pintype "bidirectional"))
    )
    (net (code "112") (name "Net-(U7-BOOT)") (class "Default")
      (node (ref "C49") (pin "1") (pinfunction "1_1") (pintype "passive"))
      (node (ref "U7") (pin "8") (pinfunction "BOOT_8") (pintype "bidirectional"))
    )
    (net (code "113") (name "Net-(U7-COMP)") (class "Default")
      (node (ref "C58") (pin "1") (pinfunction "1_1") (pintype "passive"))
      (node (ref "C63") (pin "1") (pinfunction "1_1") (pintype "passive"))
      (node (ref "U7") (pin "3") (pinfunction "COMP_3") (pintype "bidirectional"))
    )
    (net (code "114") (name "Net-(U7-FB)") (class "Default")
      (node (ref "C53") (pin "2") (pinfunction "2_2") (pintype "passive"))
      (node (ref "C63") (pin "2") (pinfunction "2_2") (pintype "passive"))
      (node (ref "R48") (pin "1") (pinfunction "1_1") (pintype "passive"))
      (node (ref "R49") (pin "2") (pinfunction "2_2") (pintype "passive"))
      (node (ref "R55") (pin "1") (pinfunction "1_1") (pintype "passive"))
      (node (ref "R80") (pin "1") (pinfunction "1_1") (pintype "passive"))
      (node (ref "U7") (pin "2") (pinfunction "FB_2") (pintype "bidirectional"))
    )
    (net (code "115") (name "Net-(U7-VCC)") (class "Default")
      (node (ref "C107") (pin "1") (pinfunction "1_1") (pintype "passive"))
      (node (ref "U7") (pin "6") (pinfunction "VCC_6") (pintype "bidirectional"))
    )
    (net (code "116") (name "Net-(U7-VIN)") (class "Default")
      (node (ref "C48") (pin "1") (pinfunction "1_1") (pintype "passive"))
      (node (ref "R47") (pin "2") (pinfunction "2_2") (pintype "passive"))
      (node (ref "U7") (pin "4") (pinfunction "VIN_4") (pintype "bidirectional"))
    )
    (net (code "117") (name "Net-(U8-BOOT)") (class "Default")
      (node (ref "C54") (pin "1") (pinfunction "1_1") (pintype "passive"))
      (node (ref "U8") (pin "8") (pinfunction "BOOT_8") (pintype "bidirectional"))
    )
    (net (code "118") (name "Net-(U8-COMP)") (class "Default")
      (node (ref "C64") (pin "1") (pinfunction "1_1") (pintype "passive"))
      (node (ref "C65") (pin "1") (pinfunction "1_1") (pintype "passive"))
      (node (ref "U8") (pin "3") (pinfunction "COMP_3") (pintype "bidirectional"))
    )
    (net (code "119") (name "Net-(U8-FB)") (class "Default")
      (node (ref "C59") (pin "2") (pinfunction "2_2") (pintype "passive"))
      (node (ref "C65") (pin "2") (pinfunction "2_2") (pintype "passive"))
      (node (ref "R52") (pin "1") (pinfunction "1_1") (pintype "passive"))
      (node (ref "R56") (pin "1") (pinfunction "1_1") (pintype "passive"))
      (node (ref "R57") (pin "2") (pinfunction "2_2") (pintype "passive"))
      (node (ref "U8") (pin "2") (pinfunction "FB_2") (pintype "bidirectional"))
    )
    (net (code "120") (name "Net-(U8-VCC)") (class "Default")
      (node (ref "C94") (pin "1") (pinfunction "1_1") (pintype "passive"))
      (node (ref "U8") (pin "6") (pinfunction "VCC_6") (pintype "bidirectional"))
    )
    (net (code "121") (name "Net-(U8-VIN)") (class "Default")
      (node (ref "C52") (pin "1") (pinfunction "1_1") (pintype "passive"))
      (node (ref "R46") (pin "2") (pinfunction "2_2") (pintype "passive"))
      (node (ref "U8") (pin "4") (pinfunction "VIN_4") (pintype "bidirectional"))
    )
    (net (code "122") (name "Net-(U9-VM)") (class "Default")
      (node (ref "F5") (pin "2") (pinfunction "2_2") (pintype "bidirectional"))
      (node (ref "R61") (pin "1") (pinfunction "1_1") (pintype "passive"))
      (node (ref "U9") (pin "4") (pinfunction "VM_4") (pintype "bidirectional"))
    )
    (net (code "123") (name "Net-(U9-VP)") (class "Default")
      (node (ref "D14") (pin "C") (pinfunction "C_C") (pintype "passive"))
      (node (ref "R61") (pin "2") (pinfunction "2_2") (pintype "passive"))
      (node (ref "U9") (pin "3") (pinfunction "VP_3") (pintype "bidirectional"))
    )
    (net (code "124") (name "Net-(U10-BOOT)") (class "Default")
      (node (ref "C73") (pin "1") (pinfunction "1_1") (pintype "passive"))
      (node (ref "U10") (pin "8") (pinfunction "BOOT_8") (pintype "bidirectional"))
    )
    (net (code "125") (name "Net-(U10-COMP)") (class "Default")
      (node (ref "C86") (pin "1") (pinfunction "1_1") (pintype "passive"))
      (node (ref "C88") (pin "1") (pinfunction "1_1") (pintype "passive"))
      (node (ref "U10") (pin "3") (pinfunction "COMP_3") (pintype "bidirectional"))
    )
    (net (code "126") (name "Net-(U10-FB)") (class "Default")
      (node (ref "C77") (pin "2") (pinfunction "2_2") (pintype "passive"))
      (node (ref "C88") (pin "2") (pinfunction "2_2") (pintype "passive"))
      (node (ref "R65") (pin "1") (pinfunction "1_1") (pintype "passive"))
      (node (ref "R69") (pin "1") (pinfunction "1_1") (pintype "passive"))
      (node (ref "R70") (pin "2") (pinfunction "2_2") (pintype "passive"))
      (node (ref "U10") (pin "2") (pinfunction "FB_2") (pintype "bidirectional"))
    )
    (net (code "127") (name "Net-(U10-VCC)") (class "Default")
      (node (ref "C95") (pin "1") (pinfunction "1_1") (pintype "passive"))
      (node (ref "U10") (pin "6") (pinfunction "VCC_6") (pintype "bidirectional"))
    )
    (net (code "128") (name "Net-(U10-VIN)") (class "Default")
      (node (ref "C72") (pin "1") (pinfunction "1_1") (pintype "passive"))
      (node (ref "R62") (pin "2") (pinfunction "2_2") (pintype "passive"))
      (node (ref "U10") (pin "4") (pinfunction "VIN_4") (pintype "bidirectional"))
    )
    (net (code "129") (name "Net-(U11-VOUT)") (class "Default")
      (node (ref "C87") (pin "1") (pinfunction "1_1") (pintype "passive"))
      (node (ref "U11") (pin "3") (pinfunction "VOUT_3") (pintype "bidirectional"))
      (node (ref "U14") (pin "1") (pinfunction "VIN_1") (pintype "bidirectional"))
    )
    (net (code "130") (name "Net-(U12-IN-)") (class "Default")
      (node (ref "R31") (pin "2") (pinfunction "2_2") (pintype "passive"))
      (node (ref "U12") (pin "3") (pinfunction "IN-_3") (pintype "input"))
      (node (ref "U12") (pin "4") (pinfunction "OUT_4") (pintype "output"))
    )
    (net (code "131") (name "Net-(U13-IN-)") (class "Default")
      (node (ref "R35") (pin "2") (pinfunction "2_2") (pintype "passive"))
      (node (ref "U13") (pin "3") (pinfunction "IN-_3") (pintype "input"))
      (node (ref "U13") (pin "4") (pinfunction "OUT_4") (pintype "output"))
    )
    (net (code "132") (name "Net-(U15-VM)") (class "Default")
      (node (ref "F6") (pin "2") (pinfunction "2_2") (pintype "bidirectional"))
      (node (ref "R79") (pin "1") (pinfunction "1_1") (pintype "passive"))
      (node (ref "U15") (pin "4") (pinfunction "VM_4") (pintype "bidirectional"))
    )
    (net (code "133") (name "Net-(U15-VP)") (class "Default")
      (node (ref "D16") (pin "C") (pinfunction "C_C") (pintype "passive"))
      (node (ref "R79") (pin "2") (pinfunction "2_2") (pintype "passive"))
      (node (ref "U15") (pin "3") (pinfunction "VP_3") (pintype "bidirectional"))
    )
    (net (code "134") (name "Net-(U16-IN-)") (class "Default")
      (node (ref "R80") (pin "2") (pinfunction "2_2") (pintype "passive"))
      (node (ref "U16") (pin "3") (pinfunction "IN-_3") (pintype "input"))
      (node (ref "U16") (pin "4") (pinfunction "OUT_4") (pintype "output"))
    )
    (net (code "135") (name "unconnected-(U2-PWRGD-Pad5)") (class "Default")
      (node (ref "U2") (pin "5") (pinfunction "PWRGD_5") (pintype "bidirectional"))
    )
    (net (code "136") (name "unconnected-(U5-PWRGD-Pad5)") (class "Default")
      (node (ref "U5") (pin "5") (pinfunction "PWRGD_5") (pintype "bidirectional"))
    )
    (net (code "137") (name "unconnected-(U7-PWRGD-Pad5)") (class "Default")
      (node (ref "U7") (pin "5") (pinfunction "PWRGD_5") (pintype "bidirectional"))
    )
    (net (code "138") (name "unconnected-(U8-PWRGD-Pad5)") (class "Default")
      (node (ref "U8") (pin "5") (pinfunction "PWRGD_5") (pintype "bidirectional"))
    )
    (net (code "139") (name "unconnected-(U10-PWRGD-Pad5)") (class "Default")
      (node (ref "U10") (pin "5") (pinfunction "PWRGD_5") (pintype "bidirectional"))
    )
  )
)
